# elasticNode.net
KiCad netlist of a schematic drawn in EAGLE
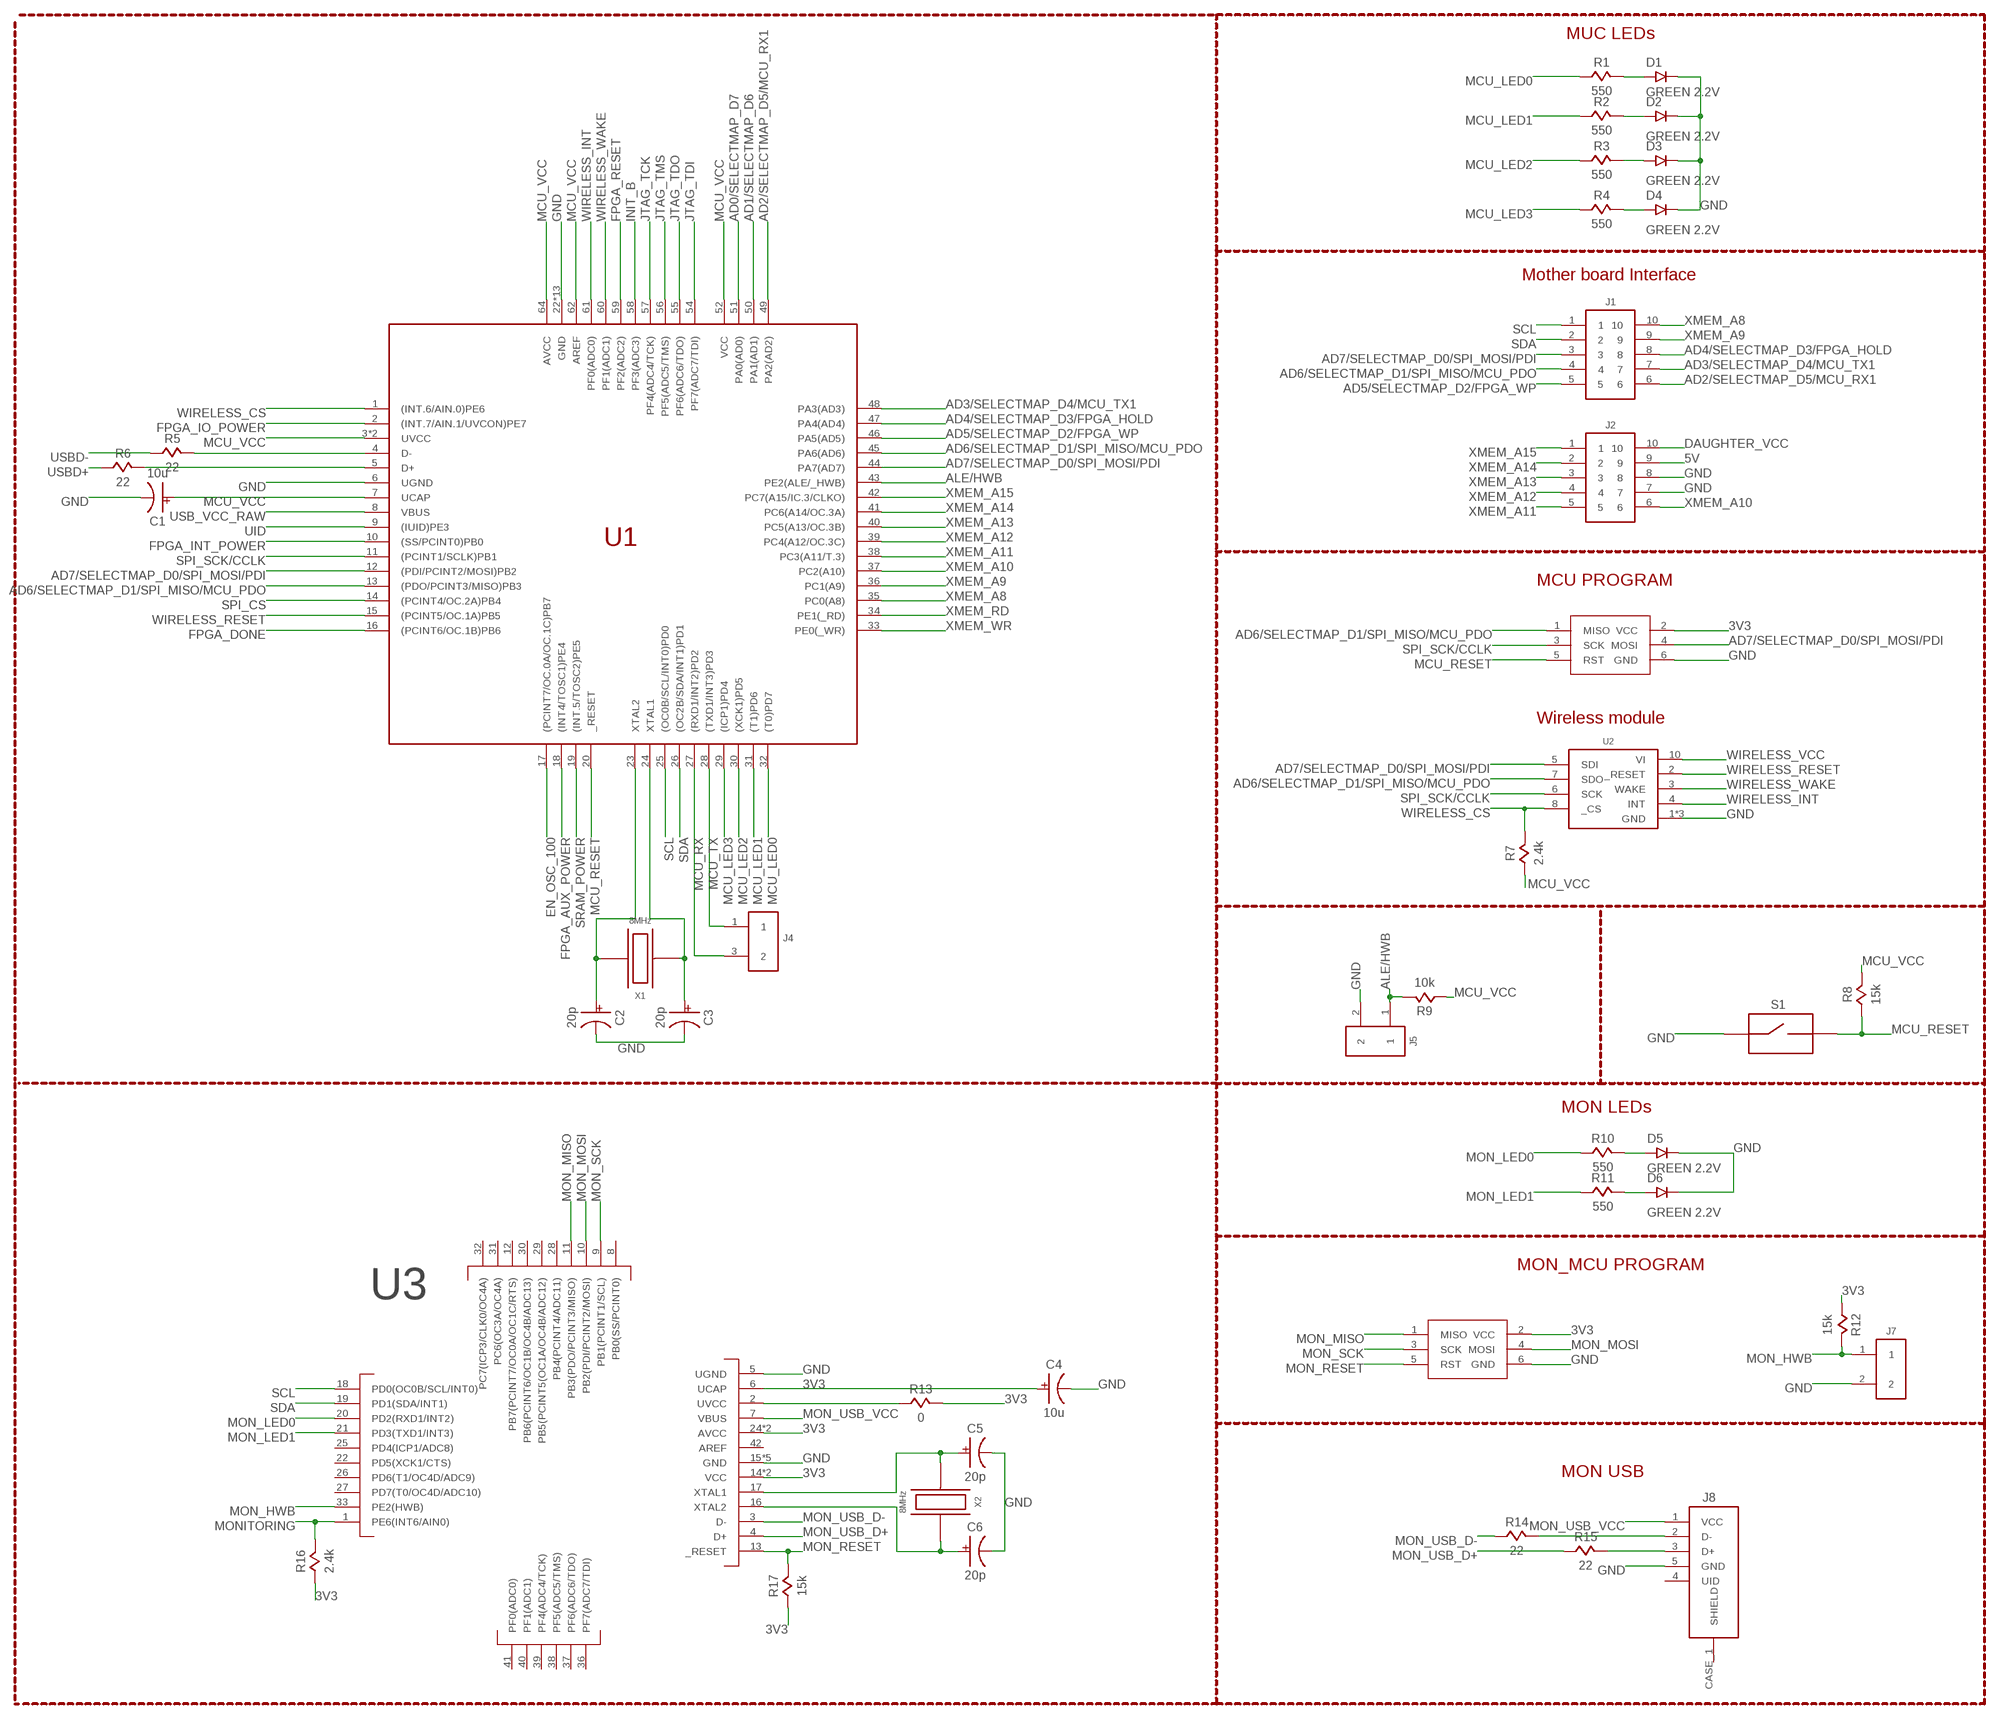
[diagram p0: schematic, sheet 1]
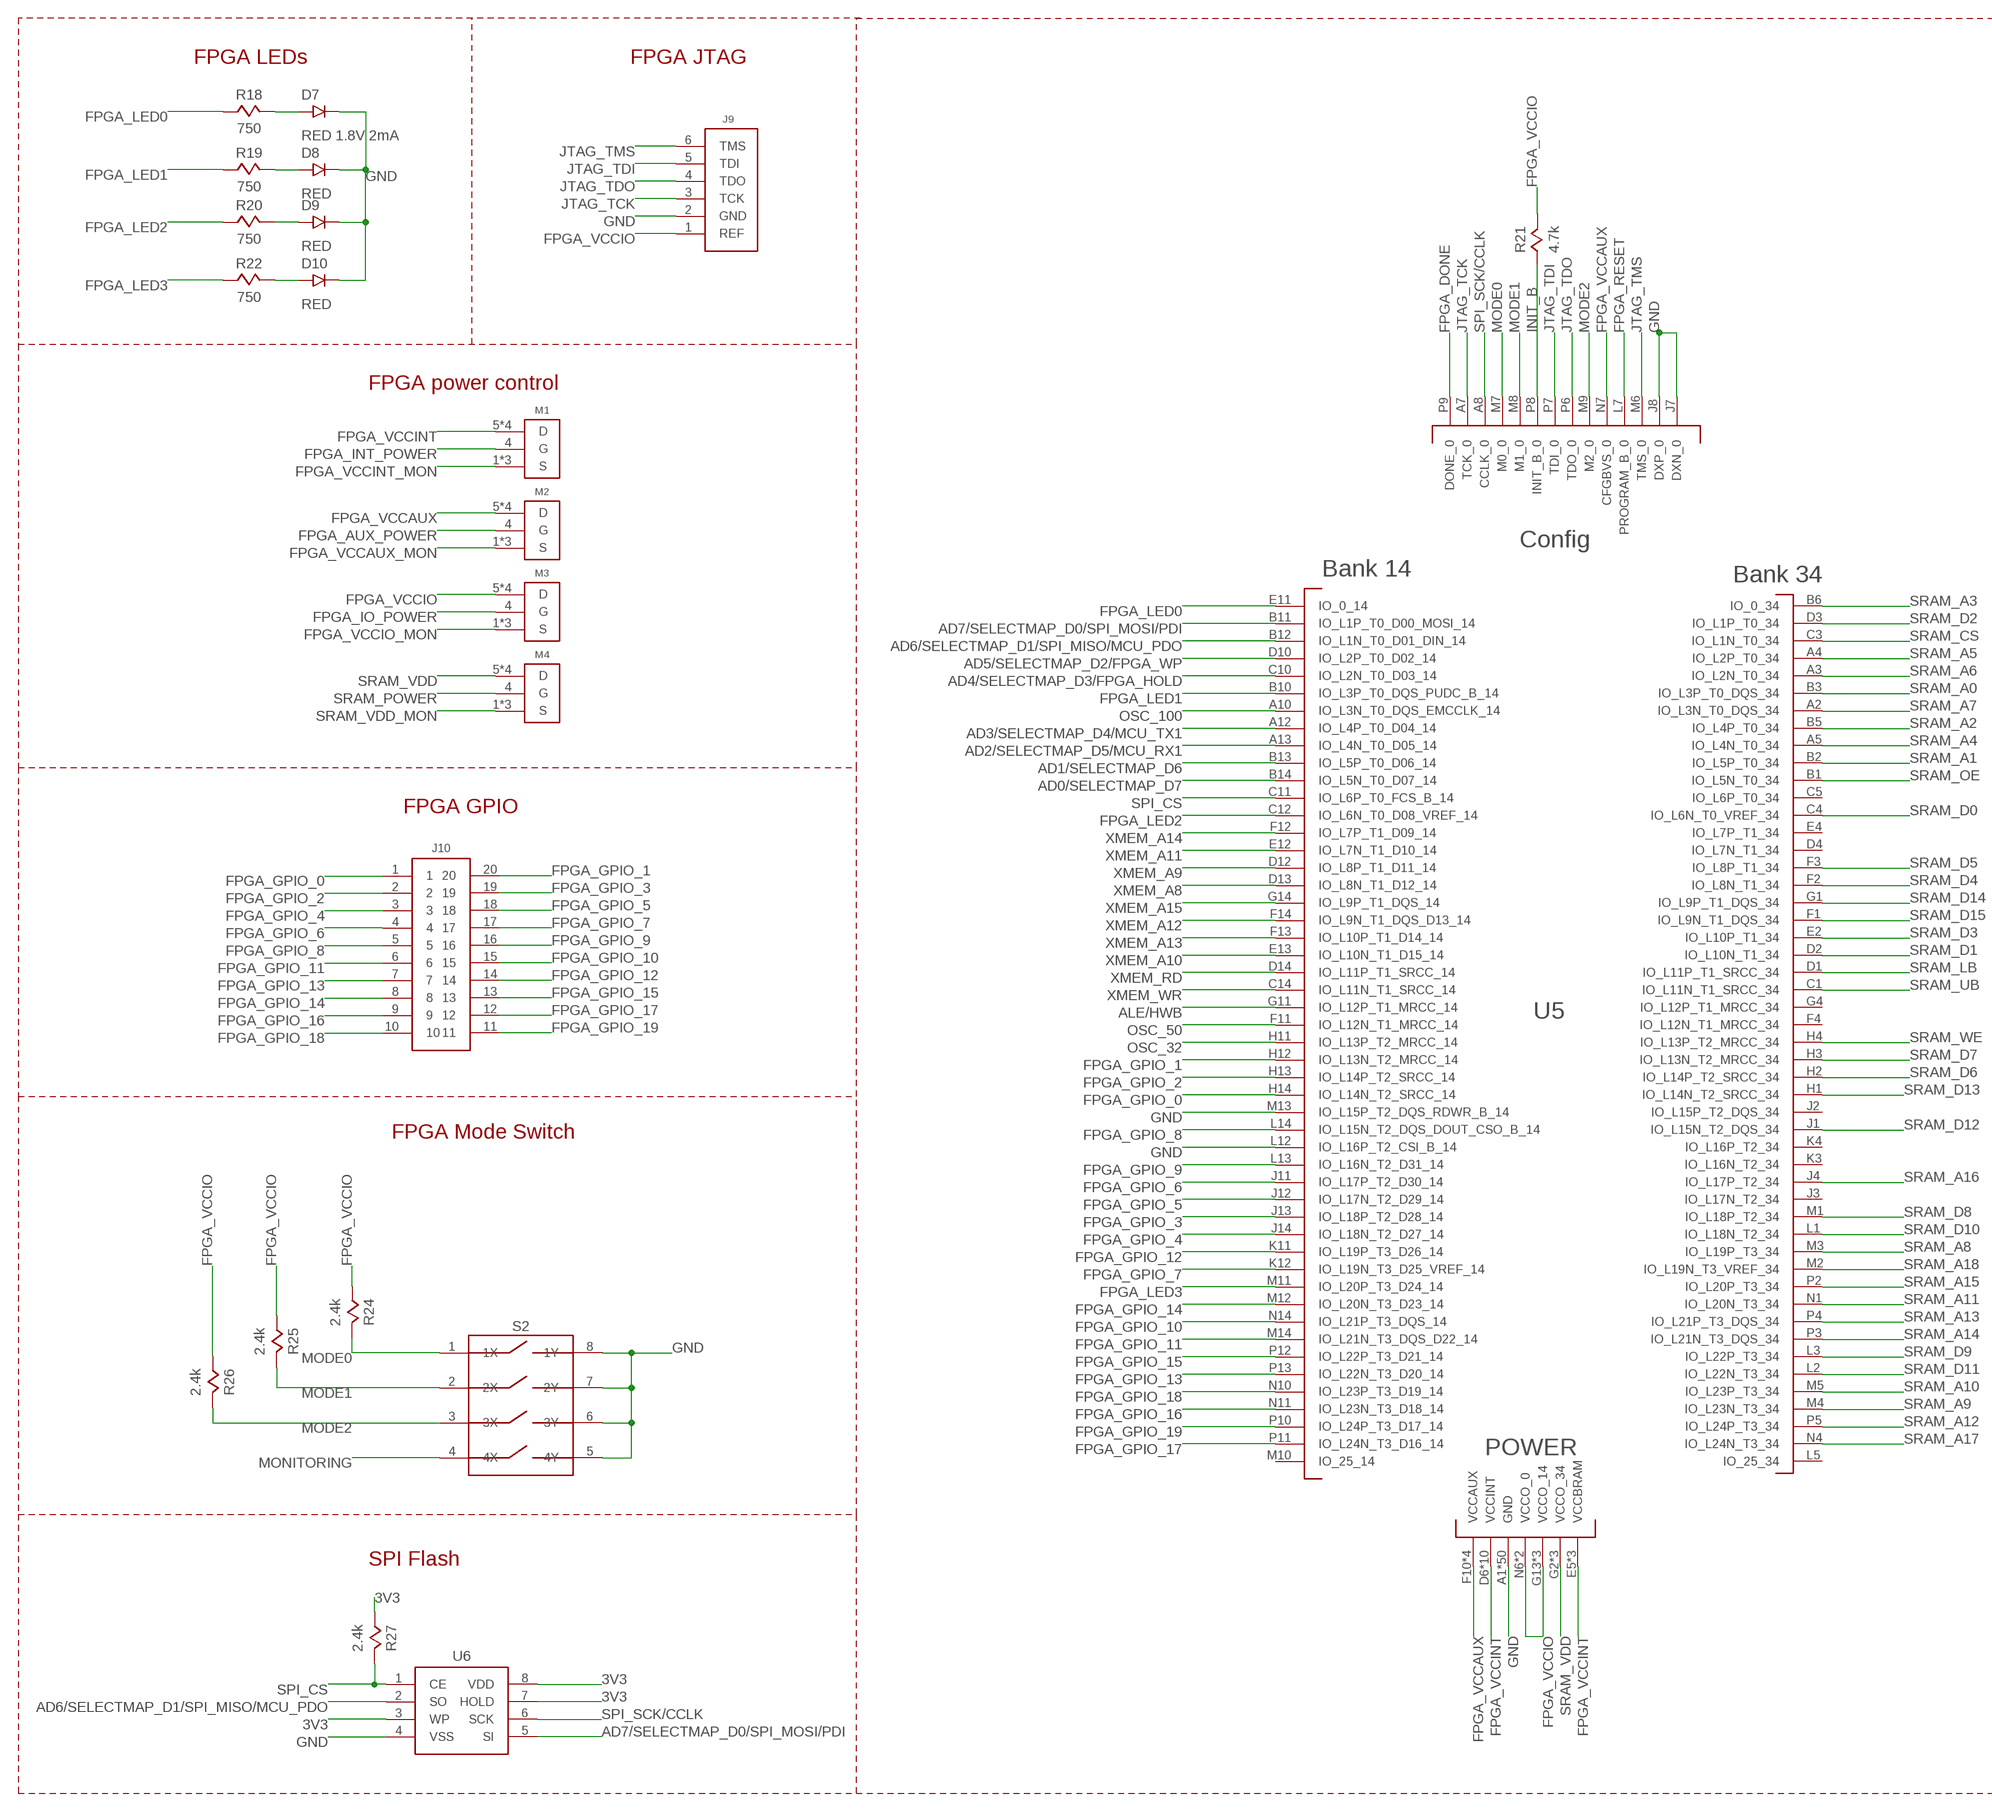
[diagram p1: schematic, sheet 2, part 1 of 2]
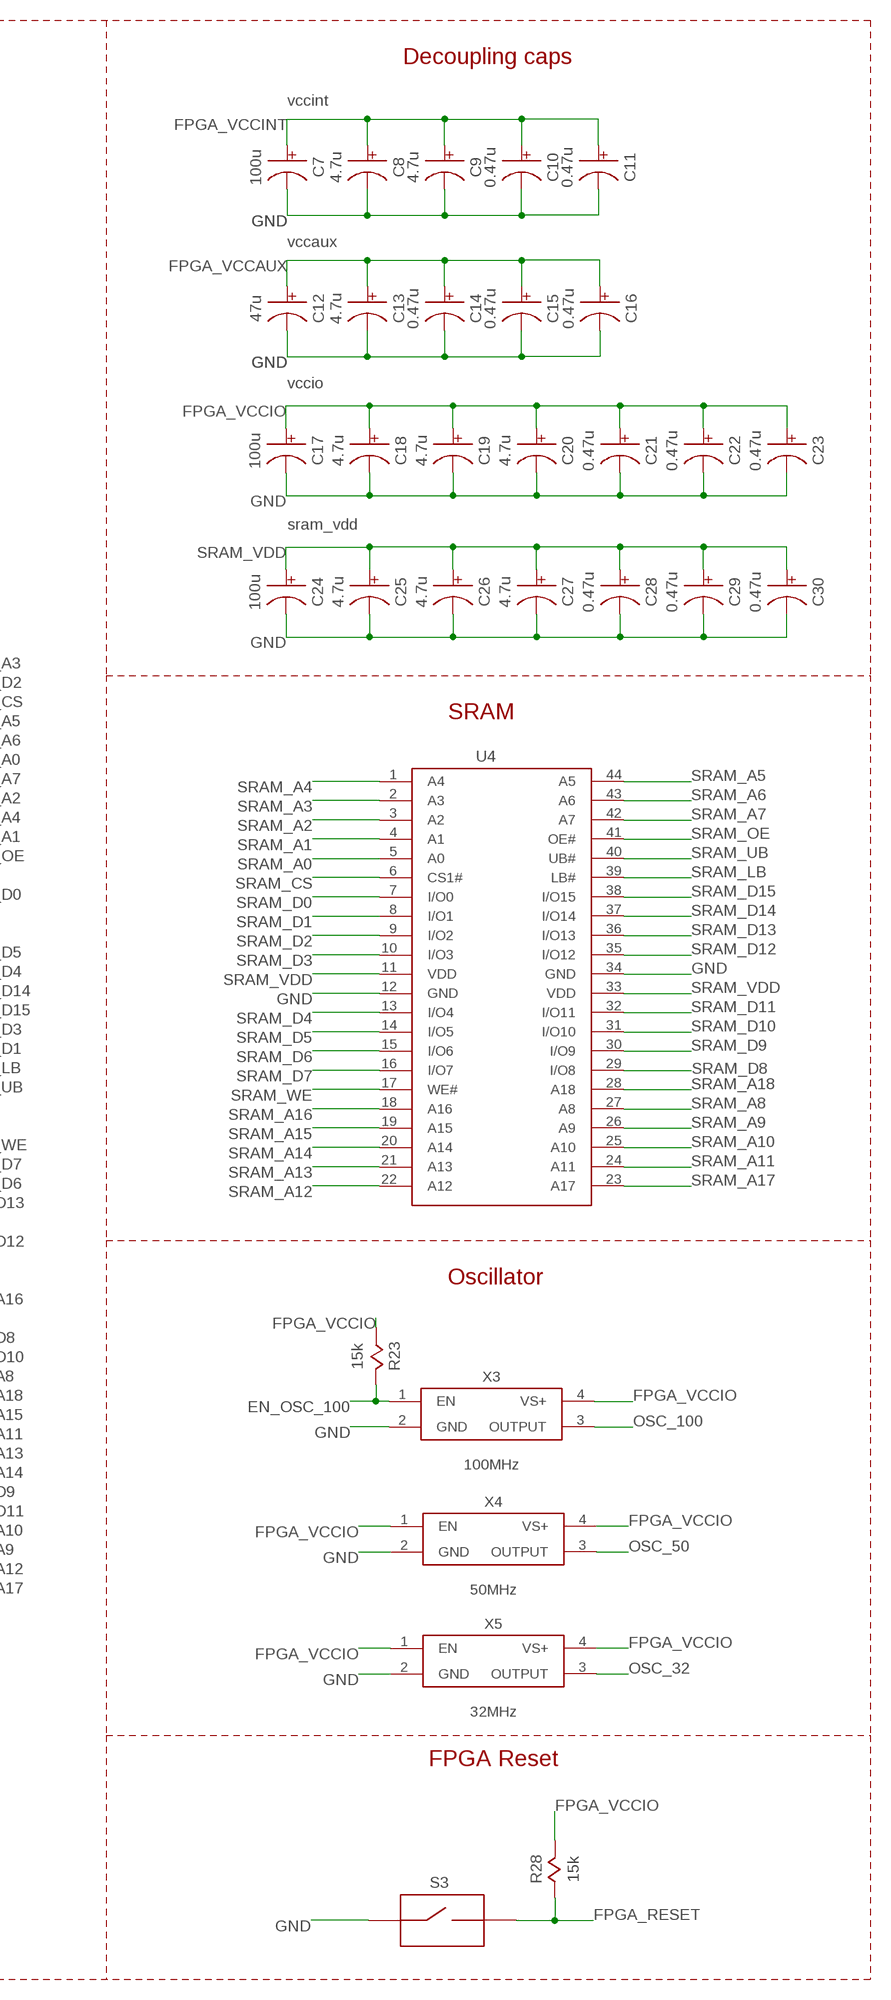
[diagram p2: schematic, sheet 2, part 2 of 2]
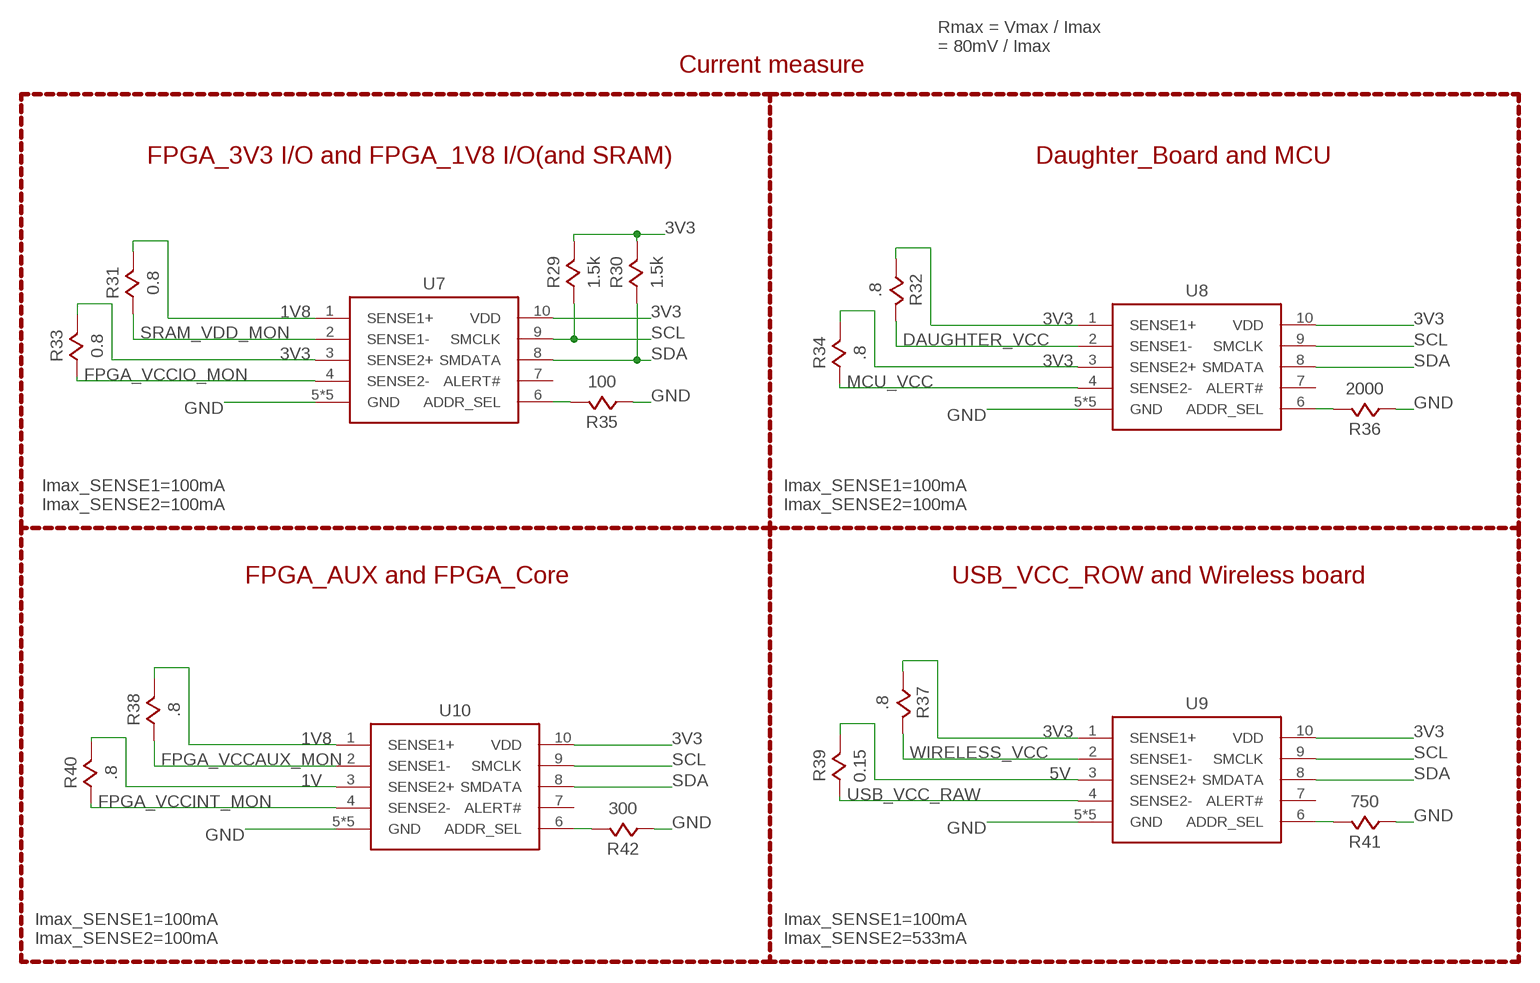
[diagram p3: schematic, sheet 3]
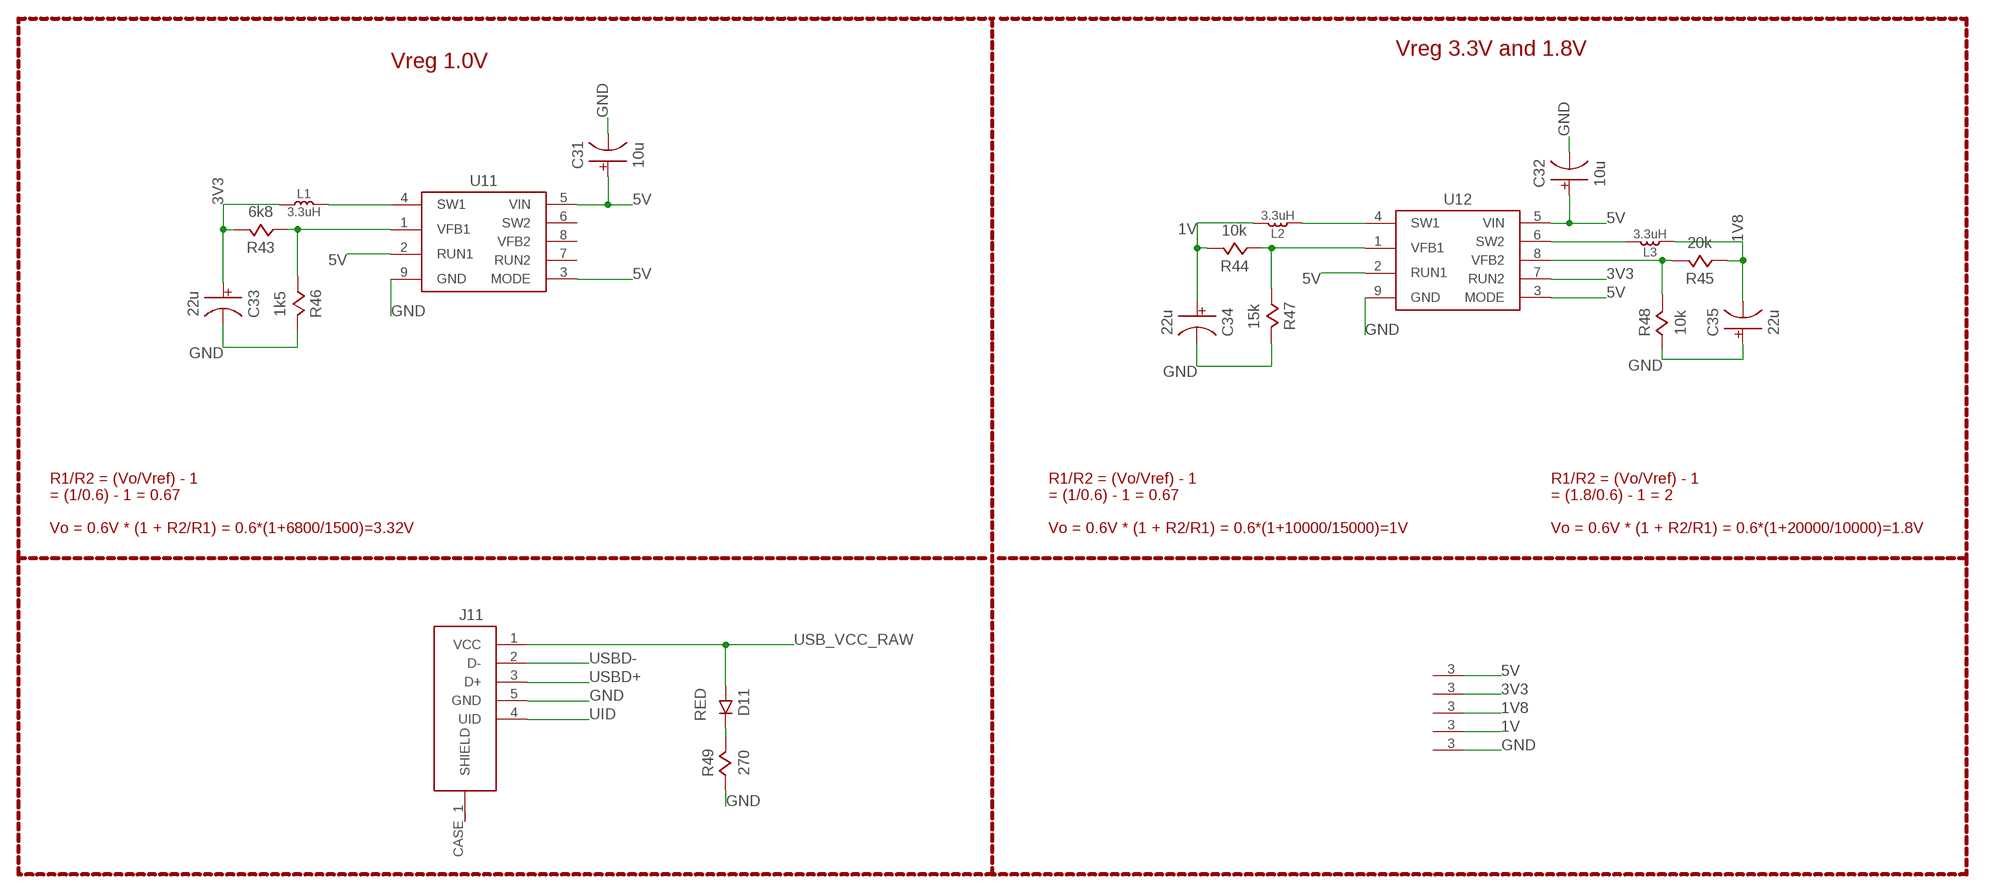
[diagram p4: schematic, sheet 4]

(export (version "E")
  (design (tool "Eeschema 10.0.6"))
  (components
    (comp (ref "C7")
      (value "100u")
      (footprint "eagle-import:1210")
      (libsource (lib "eagle-import") (part "CAPACITOR1210"))
    )
    (comp (ref "C8")
      (value "4.7u")
      (footprint "eagle-import:0805")
      (libsource (lib "eagle-import") (part "CAPACITOR0805"))
    )
    (comp (ref "C9")
      (value "4.7u")
      (footprint "eagle-import:0805")
      (libsource (lib "eagle-import") (part "CAPACITOR0805"))
    )
    (comp (ref "C10")
      (value "0.47u")
      (footprint "eagle-import:0805")
      (libsource (lib "eagle-import") (part "CAPACITOR0805"))
    )
    (comp (ref "C11")
      (value "0.47u")
      (footprint "eagle-import:0805")
      (libsource (lib "eagle-import") (part "CAPACITOR0805"))
    )
    (comp (ref "C12")
      (value "47u")
      (footprint "eagle-import:1210")
      (libsource (lib "eagle-import") (part "CAPACITOR1210"))
    )
    (comp (ref "C13")
      (value "4.7u")
      (footprint "eagle-import:0805")
      (libsource (lib "eagle-import") (part "CAPACITOR0805"))
    )
    (comp (ref "C14")
      (value "0.47u")
      (footprint "eagle-import:0805")
      (libsource (lib "eagle-import") (part "CAPACITOR0805"))
    )
    (comp (ref "C15")
      (value "0.47u")
      (footprint "eagle-import:0805")
      (libsource (lib "eagle-import") (part "CAPACITOR0805"))
    )
    (comp (ref "C16")
      (value "0.47u")
      (footprint "eagle-import:0805")
      (libsource (lib "eagle-import") (part "CAPACITOR0805"))
    )
    (comp (ref "C17")
      (value "100u")
      (footprint "eagle-import:1210")
      (libsource (lib "eagle-import") (part "CAPACITOR1210"))
    )
    (comp (ref "C18")
      (value "4.7u")
      (footprint "eagle-import:0805")
      (libsource (lib "eagle-import") (part "CAPACITOR0805"))
    )
    (comp (ref "C19")
      (value "4.7u")
      (footprint "eagle-import:0805")
      (libsource (lib "eagle-import") (part "CAPACITOR0805"))
    )
    (comp (ref "C20")
      (value "4.7u")
      (footprint "eagle-import:0805")
      (libsource (lib "eagle-import") (part "CAPACITOR0805"))
    )
    (comp (ref "C21")
      (value "0.47u")
      (footprint "eagle-import:0805")
      (libsource (lib "eagle-import") (part "CAPACITOR0805"))
    )
    (comp (ref "C22")
      (value "0.47u")
      (footprint "eagle-import:0805")
      (libsource (lib "eagle-import") (part "CAPACITOR0805"))
    )
    (comp (ref "C23")
      (value "0.47u")
      (footprint "eagle-import:0805")
      (libsource (lib "eagle-import") (part "CAPACITOR0805"))
    )
    (comp (ref "C24")
      (value "100u")
      (footprint "eagle-import:1210")
      (libsource (lib "eagle-import") (part "CAPACITOR1210"))
    )
    (comp (ref "C25")
      (value "4.7u")
      (footprint "eagle-import:0805")
      (libsource (lib "eagle-import") (part "CAPACITOR0805"))
    )
    (comp (ref "C26")
      (value "4.7u")
      (footprint "eagle-import:0805")
      (libsource (lib "eagle-import") (part "CAPACITOR0805"))
    )
    (comp (ref "C27")
      (value "4.7u")
      (footprint "eagle-import:0805")
      (libsource (lib "eagle-import") (part "CAPACITOR0805"))
    )
    (comp (ref "C28")
      (value "0.47u")
      (footprint "eagle-import:0805")
      (libsource (lib "eagle-import") (part "CAPACITOR0805"))
    )
    (comp (ref "C29")
      (value "0.47u")
      (footprint "eagle-import:0805")
      (libsource (lib "eagle-import") (part "CAPACITOR0805"))
    )
    (comp (ref "C30")
      (value "0.47u")
      (footprint "eagle-import:0805")
      (libsource (lib "eagle-import") (part "CAPACITOR0805"))
    )
    (comp (ref "D7")
      (value "RED 1.8V 2mA")
      (footprint "eagle-import:0805")
      (libsource (lib "eagle-import") (part "LED"))
    )
    (comp (ref "D8")
      (value "RED")
      (footprint "eagle-import:0805")
      (libsource (lib "eagle-import") (part "LED"))
    )
    (comp (ref "D9")
      (value "RED")
      (footprint "eagle-import:0805")
      (libsource (lib "eagle-import") (part "LED"))
    )
    (comp (ref "D10")
      (value "RED")
      (footprint "eagle-import:0805")
      (libsource (lib "eagle-import") (part "LED"))
    )
    (comp (ref "J9")
      (value "JTAG_CONN_6PINSMT")
      (footprint "eagle-import:6X1_JTAG")
      (libsource (lib "eagle-import") (part "JTAG_CONN_6PINSMT"))
    )
    (comp (ref "J10")
      (value "FEMALE_HEADER_10X2")
      (footprint "eagle-import:10X2_HEADER_SMT")
      (libsource (lib "eagle-import") (part "FEMALE_HEADER_10X2"))
    )
    (comp (ref "M1")
      (value "SISS23DN")
      (footprint "eagle-import:POWERPAK1212-8")
      (libsource (lib "eagle-import") (part "SISS23DN"))
    )
    (comp (ref "M2")
      (value "SISS23DN")
      (footprint "eagle-import:POWERPAK1212-8")
      (libsource (lib "eagle-import") (part "SISS23DN"))
    )
    (comp (ref "M3")
      (value "SISS23DN")
      (footprint "eagle-import:POWERPAK1212-8")
      (libsource (lib "eagle-import") (part "SISS23DN"))
    )
    (comp (ref "M4")
      (value "SISS23DN")
      (footprint "eagle-import:POWERPAK1212-8")
      (libsource (lib "eagle-import") (part "SISS23DN"))
    )
    (comp (ref "R18")
      (value "750")
      (footprint "eagle-import:0805")
      (libsource (lib "eagle-import") (part "RESISTOR"))
    )
    (comp (ref "R19")
      (value "750")
      (footprint "eagle-import:0805")
      (libsource (lib "eagle-import") (part "RESISTOR"))
    )
    (comp (ref "R20")
      (value "750")
      (footprint "eagle-import:0805")
      (libsource (lib "eagle-import") (part "RESISTOR"))
    )
    (comp (ref "R21")
      (value "4.7k")
      (footprint "eagle-import:0805")
      (libsource (lib "eagle-import") (part "RESISTOR"))
    )
    (comp (ref "R22")
      (value "750")
      (footprint "eagle-import:0805")
      (libsource (lib "eagle-import") (part "RESISTOR"))
    )
    (comp (ref "R23")
      (value "15k")
      (footprint "eagle-import:0805")
      (libsource (lib "eagle-import") (part "RESISTOR"))
    )
    (comp (ref "R24")
      (value "2.4k")
      (footprint "eagle-import:0805")
      (libsource (lib "eagle-import") (part "RESISTOR"))
    )
    (comp (ref "R25")
      (value "2.4k")
      (footprint "eagle-import:0805")
      (libsource (lib "eagle-import") (part "RESISTOR"))
    )
    (comp (ref "R26")
      (value "2.4k")
      (footprint "eagle-import:0805")
      (libsource (lib "eagle-import") (part "RESISTOR"))
    )
    (comp (ref "R27")
      (value "2.4k")
      (footprint "eagle-import:0805")
      (libsource (lib "eagle-import") (part "RESISTOR"))
    )
    (comp (ref "R28")
      (value "15k")
      (footprint "eagle-import:0805")
      (libsource (lib "eagle-import") (part "RESISTOR"))
    )
    (comp (ref "S2")
      (value "SPST_DIP_4")
      (footprint "eagle-import:SPST_DIP4_SMT")
      (libsource (lib "eagle-import") (part "SPST_DIP_4"))
    )
    (comp (ref "S3")
      (value "SPST_BUTTON2PIN_SMT")
      (footprint "eagle-import:SPST_2PIN_SMT")
      (libsource (lib "eagle-import") (part "SPST_BUTTON2PIN_SMT"))
    )
    (comp (ref "U4")
      (value "IS66WV51216EALL")
      (footprint "eagle-import:TSOP44")
      (libsource (lib "eagle-import") (part "IS66WV51216EALL"))
    )
    (comp (ref "U5")
      (value "SPARTAN7-LX15")
      (footprint "eagle-import:FTGB196")
      (libsource (lib "eagle-import") (part "SPARTAN7-LX15"))
    )
    (comp (ref "U6")
      (value "SST26VF032BWDFN")
      (footprint "eagle-import:WDFN8")
      (libsource (lib "eagle-import") (part "SST26VF032BWDFN"))
    )
    (comp (ref "X3")
      (value "100MHz")
      (footprint "eagle-import:3.2X2.5_OSC")
      (libsource (lib "eagle-import") (part "OSCILLATOR3.2X2.5"))
    )
    (comp (ref "X4")
      (value "50MHz")
      (footprint "eagle-import:3.2X2.5_OSC")
      (libsource (lib "eagle-import") (part "OSCILLATOR3.2X2.5"))
    )
    (comp (ref "X5")
      (value "32MHz")
      (footprint "eagle-import:3.2X2.5_OSC")
      (libsource (lib "eagle-import") (part "OSCILLATOR3.2X2.5"))
    )
    (comp (ref "C1")
      (value "10u")
      (footprint "eagle-import:0805")
      (libsource (lib "eagle-import") (part "CAPACITOR0805"))
    )
    (comp (ref "C2")
      (value "20p")
      (footprint "eagle-import:0805")
      (libsource (lib "eagle-import") (part "CAPACITOR0805"))
    )
    (comp (ref "C3")
      (value "20p")
      (footprint "eagle-import:0805")
      (libsource (lib "eagle-import") (part "CAPACITOR0805"))
    )
    (comp (ref "C4")
      (value "10u")
      (footprint "eagle-import:0805")
      (libsource (lib "eagle-import") (part "CAPACITOR0805"))
    )
    (comp (ref "C5")
      (value "20p")
      (footprint "eagle-import:0805")
      (libsource (lib "eagle-import") (part "CAPACITOR0805"))
    )
    (comp (ref "C6")
      (value "20p")
      (footprint "eagle-import:0805")
      (libsource (lib "eagle-import") (part "CAPACITOR0805"))
    )
    (comp (ref "D1")
      (value "GREEN 2.2V")
      (footprint "eagle-import:0805")
      (libsource (lib "eagle-import") (part "LED"))
    )
    (comp (ref "D2")
      (value "GREEN 2.2V")
      (footprint "eagle-import:0805")
      (libsource (lib "eagle-import") (part "LED"))
    )
    (comp (ref "D3")
      (value "GREEN 2.2V")
      (footprint "eagle-import:0805")
      (libsource (lib "eagle-import") (part "LED"))
    )
    (comp (ref "D4")
      (value "GREEN 2.2V")
      (footprint "eagle-import:0805")
      (libsource (lib "eagle-import") (part "LED"))
    )
    (comp (ref "D5")
      (value "GREEN 2.2V")
      (footprint "eagle-import:0805")
      (libsource (lib "eagle-import") (part "LED"))
    )
    (comp (ref "D6")
      (value "GREEN 2.2V")
      (footprint "eagle-import:0805")
      (libsource (lib "eagle-import") (part "LED"))
    )
    (comp (ref "J1")
      (value "FEMALE_HEADER_5X2")
      (footprint "eagle-import:5X2_HEADER_SMT_1.27")
      (libsource (lib "eagle-import") (part "FEMALE_HEADER_5X2"))
    )
    (comp (ref "J2")
      (value "FEMALE_HEADER_5X2")
      (footprint "eagle-import:5X2_HEADER_SMT_1.27")
      (libsource (lib "eagle-import") (part "FEMALE_HEADER_5X2"))
    )
    (comp (ref "J3")
      (value "ISP_CONN_6PIN")
      (footprint "eagle-import:ICSP_SMT")
      (fields (field (name "SPICEPREFIX") "X"))
      (libsource (lib "eagle-import") (part "ISP_CONN_6PIN"))
    )
    (comp (ref "J4")
      (value "FEMALE_HEADER_2X1")
      (footprint "eagle-import:2X1_HEADER")
      (libsource (lib "eagle-import") (part "FEMALE_HEADER_2X1"))
    )
    (comp (ref "J5")
      (value "JUMPER")
      (footprint "eagle-import:JUMPER_SMT")
      (libsource (lib "eagle-import") (part "JUMPER"))
    )
    (comp (ref "J6")
      (value "ISP_CONN_6PIN")
      (footprint "eagle-import:ICSP_SMT")
      (libsource (lib "eagle-import") (part "ISP_CONN_6PIN"))
    )
    (comp (ref "J7")
      (value "JUMPER")
      (footprint "eagle-import:JUMPER_SMT")
      (libsource (lib "eagle-import") (part "JUMPER"))
    )
    (comp (ref "J8")
      (value "USB_CONNMICRO_SMT")
      (footprint "eagle-import:USB_MICRO_B_SMT")
      (libsource (lib "eagle-import") (part "USB_CONNMICRO_SMT"))
    )
    (comp (ref "R1")
      (value "550")
      (footprint "eagle-import:0805")
      (libsource (lib "eagle-import") (part "RESISTOR"))
    )
    (comp (ref "R2")
      (value "550")
      (footprint "eagle-import:0805")
      (libsource (lib "eagle-import") (part "RESISTOR"))
    )
    (comp (ref "R3")
      (value "550")
      (footprint "eagle-import:0805")
      (libsource (lib "eagle-import") (part "RESISTOR"))
    )
    (comp (ref "R4")
      (value "550")
      (footprint "eagle-import:0805")
      (libsource (lib "eagle-import") (part "RESISTOR"))
    )
    (comp (ref "R5")
      (value "22")
      (footprint "eagle-import:0805")
      (libsource (lib "eagle-import") (part "RESISTOR"))
    )
    (comp (ref "R6")
      (value "22")
      (footprint "eagle-import:0805")
      (libsource (lib "eagle-import") (part "RESISTOR"))
    )
    (comp (ref "R7")
      (value "2.4k")
      (footprint "eagle-import:0805")
      (libsource (lib "eagle-import") (part "RESISTOR"))
    )
    (comp (ref "R8")
      (value "15k")
      (footprint "eagle-import:0805")
      (libsource (lib "eagle-import") (part "RESISTOR"))
    )
    (comp (ref "R9")
      (value "10k")
      (footprint "eagle-import:0805")
      (libsource (lib "eagle-import") (part "RESISTOR"))
    )
    (comp (ref "R10")
      (value "550")
      (footprint "eagle-import:0805")
      (libsource (lib "eagle-import") (part "RESISTOR"))
    )
    (comp (ref "R11")
      (value "550")
      (footprint "eagle-import:0805")
      (libsource (lib "eagle-import") (part "RESISTOR"))
    )
    (comp (ref "R12")
      (value "15k")
      (footprint "eagle-import:0805")
      (libsource (lib "eagle-import") (part "RESISTOR"))
    )
    (comp (ref "R13")
      (value "0")
      (footprint "eagle-import:0805")
      (libsource (lib "eagle-import") (part "RESISTOR"))
    )
    (comp (ref "R14")
      (value "22")
      (footprint "eagle-import:0805")
      (libsource (lib "eagle-import") (part "RESISTOR"))
    )
    (comp (ref "R15")
      (value "22")
      (footprint "eagle-import:0805")
      (libsource (lib "eagle-import") (part "RESISTOR"))
    )
    (comp (ref "R16")
      (value "2.4k")
      (footprint "eagle-import:0805")
      (libsource (lib "eagle-import") (part "RESISTOR"))
    )
    (comp (ref "R17")
      (value "15k")
      (footprint "eagle-import:0805")
      (libsource (lib "eagle-import") (part "RESISTOR"))
    )
    (comp (ref "S1")
      (value "SPST_BUTTON2PIN_SMT")
      (footprint "eagle-import:SPST_2PIN_SMT")
      (libsource (lib "eagle-import") (part "SPST_BUTTON2PIN_SMT"))
    )
    (comp (ref "U1")
      (value "AT90USB128")
      (footprint "eagle-import:QFN64")
      (libsource (lib "eagle-import") (part "AT90USB128"))
    )
    (comp (ref "U2")
      (value "MRF24J40MA")
      (footprint "eagle-import:MRF24J40MA")
      (libsource (lib "eagle-import") (part "MRF24J40MA"))
    )
    (comp (ref "U3")
      (value "ATMEGA32U4QFN")
      (footprint "eagle-import:QFN44")
      (libsource (lib "eagle-import") (part "ATMEGA32U4QFN"))
    )
    (comp (ref "X1")
      (value "8MHz")
      (footprint "eagle-import:3.2X2.5_OSC")
      (libsource (lib "eagle-import") (part "QUARTZ"))
    )
    (comp (ref "X2")
      (value "8MHz")
      (footprint "eagle-import:3.2X2.5_OSC")
      (libsource (lib "eagle-import") (part "QUARTZ"))
    )
    (comp (ref "R29")
      (value "1.5k")
      (footprint "eagle-import:0805")
      (libsource (lib "eagle-import") (part "RESISTOR"))
    )
    (comp (ref "R30")
      (value "1.5k")
      (footprint "eagle-import:0805")
      (libsource (lib "eagle-import") (part "RESISTOR"))
    )
    (comp (ref "R31")
      (value "0.8")
      (footprint "eagle-import:0805")
      (libsource (lib "eagle-import") (part "RESISTOR"))
    )
    (comp (ref "R32")
      (value ".8")
      (footprint "eagle-import:0805")
      (libsource (lib "eagle-import") (part "RESISTOR"))
    )
    (comp (ref "R33")
      (value "0.8")
      (footprint "eagle-import:0805")
      (libsource (lib "eagle-import") (part "RESISTOR"))
    )
    (comp (ref "R34")
      (value ".8")
      (footprint "eagle-import:0805")
      (libsource (lib "eagle-import") (part "RESISTOR"))
    )
    (comp (ref "R35")
      (value "100")
      (footprint "eagle-import:0805")
      (libsource (lib "eagle-import") (part "RESISTOR"))
    )
    (comp (ref "R36")
      (value "2000")
      (footprint "eagle-import:0805")
      (libsource (lib "eagle-import") (part "RESISTOR"))
    )
    (comp (ref "R37")
      (value ".8")
      (footprint "eagle-import:0805")
      (libsource (lib "eagle-import") (part "RESISTOR"))
    )
    (comp (ref "R38")
      (value ".8")
      (footprint "eagle-import:0805")
      (libsource (lib "eagle-import") (part "RESISTOR"))
    )
    (comp (ref "R39")
      (value "0.15")
      (footprint "eagle-import:0805")
      (libsource (lib "eagle-import") (part "RESISTOR"))
    )
    (comp (ref "R40")
      (value ".8")
      (footprint "eagle-import:0805")
      (libsource (lib "eagle-import") (part "RESISTOR"))
    )
    (comp (ref "R41")
      (value "750")
      (footprint "eagle-import:0805")
      (libsource (lib "eagle-import") (part "RESISTOR"))
    )
    (comp (ref "R42")
      (value "300")
      (footprint "eagle-import:0805")
      (libsource (lib "eagle-import") (part "RESISTOR"))
    )
    (comp (ref "U7")
      (value "PAC1720")
      (footprint "eagle-import:VDFN10")
      (libsource (lib "eagle-import") (part "PAC1720"))
    )
    (comp (ref "U8")
      (value "PAC1720")
      (footprint "eagle-import:VDFN10")
      (libsource (lib "eagle-import") (part "PAC1720"))
    )
    (comp (ref "U9")
      (value "PAC1720")
      (footprint "eagle-import:VDFN10")
      (libsource (lib "eagle-import") (part "PAC1720"))
    )
    (comp (ref "U10")
      (value "PAC1720")
      (footprint "eagle-import:VDFN10")
      (libsource (lib "eagle-import") (part "PAC1720"))
    )
    (comp (ref "C31")
      (value "10u")
      (footprint "eagle-import:0805")
      (libsource (lib "eagle-import") (part "CAPACITOR0805"))
    )
    (comp (ref "C32")
      (value "10u")
      (footprint "eagle-import:0805")
      (libsource (lib "eagle-import") (part "CAPACITOR0805"))
    )
    (comp (ref "C33")
      (value "22u")
      (footprint "eagle-import:0805")
      (libsource (lib "eagle-import") (part "CAPACITOR0805"))
    )
    (comp (ref "C34")
      (value "22u")
      (footprint "eagle-import:0805")
      (libsource (lib "eagle-import") (part "CAPACITOR0805"))
    )
    (comp (ref "C35")
      (value "22u")
      (footprint "eagle-import:0805")
      (libsource (lib "eagle-import") (part "CAPACITOR0805"))
    )
    (comp (ref "D11")
      (value "RED")
      (footprint "eagle-import:0805")
      (libsource (lib "eagle-import") (part "LED"))
    )
    (comp (ref "J11")
      (value "USB_CONNMICRO_SMT")
      (footprint "eagle-import:USB_MICRO_B_SMT")
      (libsource (lib "eagle-import") (part "USB_CONNMICRO_SMT"))
    )
    (comp (ref "L1")
      (value "3.3uH")
      (footprint "eagle-import:0805")
      (libsource (lib "eagle-import") (part "INDUCTOR"))
    )
    (comp (ref "L2")
      (value "3.3uH")
      (footprint "eagle-import:0805")
      (libsource (lib "eagle-import") (part "INDUCTOR"))
    )
    (comp (ref "L3")
      (value "3.3uH")
      (footprint "eagle-import:0805")
      (libsource (lib "eagle-import") (part "INDUCTOR"))
    )
    (comp (ref "R43")
      (value "6k8")
      (footprint "eagle-import:0805")
      (libsource (lib "eagle-import") (part "RESISTOR"))
    )
    (comp (ref "R44")
      (value "10k")
      (footprint "eagle-import:0805")
      (libsource (lib "eagle-import") (part "RESISTOR"))
    )
    (comp (ref "R45")
      (value "20k")
      (footprint "eagle-import:0805")
      (libsource (lib "eagle-import") (part "RESISTOR"))
    )
    (comp (ref "R46")
      (value "1k5")
      (footprint "eagle-import:0805")
      (libsource (lib "eagle-import") (part "RESISTOR"))
    )
    (comp (ref "R47")
      (value "15k")
      (footprint "eagle-import:0805")
      (libsource (lib "eagle-import") (part "RESISTOR"))
    )
    (comp (ref "R48")
      (value "10k")
      (footprint "eagle-import:0805")
      (libsource (lib "eagle-import") (part "RESISTOR"))
    )
    (comp (ref "R49")
      (value "270")
      (footprint "eagle-import:0805")
      (libsource (lib "eagle-import") (part "RESISTOR"))
    )
    (comp (ref "TP1")
      (value "TEST_POINTTHT")
      (footprint "eagle-import:THT")
      (libsource (lib "eagle-import") (part "TEST_POINTTHT"))
    )
    (comp (ref "TP2")
      (value "TEST_POINTTHT")
      (footprint "eagle-import:THT")
      (libsource (lib "eagle-import") (part "TEST_POINTTHT"))
    )
    (comp (ref "TP3")
      (value "TEST_POINTTHT")
      (footprint "eagle-import:THT")
      (libsource (lib "eagle-import") (part "TEST_POINTTHT"))
    )
    (comp (ref "TP4")
      (value "TEST_POINTTHT")
      (footprint "eagle-import:THT")
      (libsource (lib "eagle-import") (part "TEST_POINTTHT"))
    )
    (comp (ref "TP5")
      (value "TEST_POINTTHT")
      (footprint "eagle-import:THT")
      (libsource (lib "eagle-import") (part "TEST_POINTTHT"))
    )
    (comp (ref "U11")
      (value "LTC3419DFN")
      (footprint "eagle-import:DFN8")
      (libsource (lib "eagle-import") (part "LTC3419DFN"))
    )
    (comp (ref "U12")
      (value "LTC3419DFN")
      (footprint "eagle-import:DFN8")
      (libsource (lib "eagle-import") (part "LTC3419DFN"))
    )
  )
  (nets
    (net (code "1") (name "1V") (class "Default")
      (node (ref "C34") (pin "1") (pinfunction "P$1_1") (pintype "bidirectional"))
      (node (ref "L2") (pin "2") (pinfunction "P$2_2") (pintype "bidirectional"))
      (node (ref "R40") (pin "2") (pinfunction "2_2") (pintype "bidirectional"))
      (node (ref "R44") (pin "2") (pinfunction "2_2") (pintype "bidirectional"))
      (node (ref "TP4") (pin "3") (pinfunction ">NAME_3") (pintype "bidirectional"))
      (node (ref "U10") (pin "3") (pinfunction "SENSE2+_3") (pintype "bidirectional"))
    )
    (net (code "2") (name "1V8") (class "Default")
      (node (ref "C35") (pin "2") (pinfunction "P$2_2") (pintype "bidirectional"))
      (node (ref "L3") (pin "1") (pinfunction "P$1_1") (pintype "bidirectional"))
      (node (ref "R31") (pin "2") (pinfunction "2_2") (pintype "bidirectional"))
      (node (ref "R38") (pin "2") (pinfunction "2_2") (pintype "bidirectional"))
      (node (ref "R45") (pin "1") (pinfunction "1_1") (pintype "bidirectional"))
      (node (ref "TP3") (pin "3") (pinfunction ">NAME_3") (pintype "bidirectional"))
      (node (ref "U10") (pin "1") (pinfunction "SENSE1+_1") (pintype "bidirectional"))
      (node (ref "U7") (pin "1") (pinfunction "SENSE1+_1") (pintype "bidirectional"))
    )
    (net (code "3") (name "3V3") (class "Default")
      (node (ref "C33") (pin "1") (pinfunction "P$1_1") (pintype "bidirectional"))
      (node (ref "C4") (pin "1") (pinfunction "P$1_1") (pintype "bidirectional"))
      (node (ref "J3") (pin "2") (pinfunction "VCC_2") (pintype "bidirectional"))
      (node (ref "J6") (pin "2") (pinfunction "VCC_2") (pintype "bidirectional"))
      (node (ref "L1") (pin "1") (pinfunction "P$1_1") (pintype "bidirectional"))
      (node (ref "R12") (pin "1") (pinfunction "1_1") (pintype "bidirectional"))
      (node (ref "R13") (pin "2") (pinfunction "2_2") (pintype "bidirectional"))
      (node (ref "R16") (pin "1") (pinfunction "1_1") (pintype "bidirectional"))
      (node (ref "R17") (pin "1") (pinfunction "1_1") (pintype "bidirectional"))
      (node (ref "R27") (pin "1") (pinfunction "1_1") (pintype "bidirectional"))
      (node (ref "R29") (pin "2") (pinfunction "2_2") (pintype "bidirectional"))
      (node (ref "R30") (pin "2") (pinfunction "2_2") (pintype "bidirectional"))
      (node (ref "R32") (pin "2") (pinfunction "2_2") (pintype "bidirectional"))
      (node (ref "R33") (pin "2") (pinfunction "2_2") (pintype "bidirectional"))
      (node (ref "R34") (pin "2") (pinfunction "2_2") (pintype "bidirectional"))
      (node (ref "R37") (pin "2") (pinfunction "2_2") (pintype "bidirectional"))
      (node (ref "R43") (pin "2") (pinfunction "2_2") (pintype "bidirectional"))
      (node (ref "TP2") (pin "3") (pinfunction ">NAME_3") (pintype "bidirectional"))
      (node (ref "U10") (pin "10") (pinfunction "VDD_10") (pintype "bidirectional"))
      (node (ref "U12") (pin "7") (pinfunction "RUN2_7") (pintype "bidirectional"))
      (node (ref "U3") (pin "14") (pinfunction "VCC_14") (pintype "bidirectional"))
      (node (ref "U3") (pin "24") (pinfunction "AVCC_24") (pintype "bidirectional"))
      (node (ref "U3") (pin "34") (pinfunction "VCC_34") (pintype "bidirectional"))
      (node (ref "U3") (pin "44") (pinfunction "AVCC_44") (pintype "bidirectional"))
      (node (ref "U3") (pin "6") (pinfunction "UCAP_6") (pintype "bidirectional"))
      (node (ref "U6") (pin "3") (pinfunction "WP_3") (pintype "bidirectional"))
      (node (ref "U6") (pin "7") (pinfunction "HOLD_7") (pintype "bidirectional"))
      (node (ref "U6") (pin "8") (pinfunction "VDD_8") (pintype "bidirectional"))
      (node (ref "U7") (pin "10") (pinfunction "VDD_10") (pintype "bidirectional"))
      (node (ref "U7") (pin "3") (pinfunction "SENSE2+_3") (pintype "bidirectional"))
      (node (ref "U8") (pin "1") (pinfunction "SENSE1+_1") (pintype "bidirectional"))
      (node (ref "U8") (pin "10") (pinfunction "VDD_10") (pintype "bidirectional"))
      (node (ref "U8") (pin "3") (pinfunction "SENSE2+_3") (pintype "bidirectional"))
      (node (ref "U9") (pin "1") (pinfunction "SENSE1+_1") (pintype "bidirectional"))
      (node (ref "U9") (pin "10") (pinfunction "VDD_10") (pintype "bidirectional"))
    )
    (net (code "4") (name "5V") (class "Default")
      (node (ref "C31") (pin "1") (pinfunction "P$1_1") (pintype "bidirectional"))
      (node (ref "C32") (pin "1") (pinfunction "P$1_1") (pintype "bidirectional"))
      (node (ref "J2") (pin "9") (pinfunction "9_9") (pintype "bidirectional"))
      (node (ref "R39") (pin "2") (pinfunction "2_2") (pintype "bidirectional"))
      (node (ref "TP1") (pin "3") (pinfunction ">NAME_3") (pintype "bidirectional"))
      (node (ref "U11") (pin "2") (pinfunction "RUN1_2") (pintype "bidirectional"))
      (node (ref "U11") (pin "3") (pinfunction "MODE_3") (pintype "bidirectional"))
      (node (ref "U11") (pin "5") (pinfunction "VIN_5") (pintype "bidirectional"))
      (node (ref "U12") (pin "2") (pinfunction "RUN1_2") (pintype "bidirectional"))
      (node (ref "U12") (pin "3") (pinfunction "MODE_3") (pintype "bidirectional"))
      (node (ref "U12") (pin "5") (pinfunction "VIN_5") (pintype "bidirectional"))
      (node (ref "U9") (pin "3") (pinfunction "SENSE2+_3") (pintype "bidirectional"))
    )
    (net (code "5") (name "AD0{slash}SELECTMAP_D7") (class "Default")
      (node (ref "U1") (pin "51") (pinfunction "PA0(AD0)_51") (pintype "bidirectional"))
      (node (ref "U5") (pin "B14") (pinfunction "IO_L5N_T0_D07_14_B14") (pintype "bidirectional"))
    )
    (net (code "6") (name "AD1{slash}SELECTMAP_D6") (class "Default")
      (node (ref "U1") (pin "50") (pinfunction "PA1(AD1)_50") (pintype "bidirectional"))
      (node (ref "U5") (pin "B13") (pinfunction "IO_L5P_T0_D06_14_B13") (pintype "bidirectional"))
    )
    (net (code "7") (name "AD2{slash}SELECTMAP_D5{slash}MCU_RX1") (class "Default")
      (node (ref "J1") (pin "6") (pinfunction "6_6") (pintype "bidirectional"))
      (node (ref "U1") (pin "49") (pinfunction "PA2(AD2)_49") (pintype "bidirectional"))
      (node (ref "U5") (pin "A13") (pinfunction "IO_L4N_T0_D05_14_A13") (pintype "bidirectional"))
    )
    (net (code "8") (name "AD3{slash}SELECTMAP_D4{slash}MCU_TX1") (class "Default")
      (node (ref "J1") (pin "7") (pinfunction "7_7") (pintype "bidirectional"))
      (node (ref "U1") (pin "48") (pinfunction "PA3(AD3)_48") (pintype "bidirectional"))
      (node (ref "U5") (pin "A12") (pinfunction "IO_L4P_T0_D04_14_A12") (pintype "bidirectional"))
    )
    (net (code "9") (name "AD4{slash}SELECTMAP_D3{slash}FPGA_HOLD") (class "Default")
      (node (ref "J1") (pin "8") (pinfunction "8_8") (pintype "bidirectional"))
      (node (ref "U1") (pin "47") (pinfunction "PA4(AD4)_47") (pintype "bidirectional"))
      (node (ref "U5") (pin "C10") (pinfunction "IO_L2N_T0_D03_14_C10") (pintype "bidirectional"))
    )
    (net (code "10") (name "AD5{slash}SELECTMAP_D2{slash}FPGA_WP") (class "Default")
      (node (ref "J1") (pin "5") (pinfunction "5_5") (pintype "bidirectional"))
      (node (ref "U1") (pin "46") (pinfunction "PA5(AD5)_46") (pintype "bidirectional"))
      (node (ref "U5") (pin "D10") (pinfunction "IO_L2P_T0_D02_14_D10") (pintype "bidirectional"))
    )
    (net (code "11") (name "AD6{slash}SELECTMAP_D1{slash}SPI_MISO{slash}MCU_PDO") (class "Default")
      (node (ref "J1") (pin "4") (pinfunction "4_4") (pintype "bidirectional"))
      (node (ref "J3") (pin "1") (pinfunction "MISO_1") (pintype "bidirectional"))
      (node (ref "U1") (pin "13") (pinfunction "(PDO/PCINT3/MISO)PB3_13") (pintype "bidirectional"))
      (node (ref "U1") (pin "45") (pinfunction "PA6(AD6)_45") (pintype "bidirectional"))
      (node (ref "U2") (pin "7") (pinfunction "SDO_7") (pintype "bidirectional"))
      (node (ref "U5") (pin "B12") (pinfunction "IO_L1N_T0_D01_DIN_14_B12") (pintype "bidirectional"))
      (node (ref "U6") (pin "2") (pinfunction "SO_2") (pintype "bidirectional"))
    )
    (net (code "12") (name "AD7{slash}SELECTMAP_D0{slash}SPI_MOSI{slash}PDI") (class "Default")
      (node (ref "J1") (pin "3") (pinfunction "3_3") (pintype "bidirectional"))
      (node (ref "J3") (pin "4") (pinfunction "MOSI_4") (pintype "bidirectional"))
      (node (ref "U1") (pin "12") (pinfunction "(PDI/PCINT2/MOSI)PB2_12") (pintype "bidirectional"))
      (node (ref "U1") (pin "44") (pinfunction "PA7(AD7)_44") (pintype "bidirectional"))
      (node (ref "U2") (pin "5") (pinfunction "SDI_5") (pintype "bidirectional"))
      (node (ref "U5") (pin "B11") (pinfunction "IO_L1P_T0_D00_MOSI_14_B11") (pintype "bidirectional"))
      (node (ref "U6") (pin "5") (pinfunction "SI_5") (pintype "bidirectional"))
    )
    (net (code "13") (name "ALE{slash}HWB") (class "Default")
      (node (ref "J5") (pin "1") (pinfunction "1_1") (pintype "bidirectional"))
      (node (ref "R9") (pin "2") (pinfunction "2_2") (pintype "bidirectional"))
      (node (ref "U1") (pin "43") (pinfunction "PE2(ALE/_HWB)_43") (pintype "bidirectional"))
      (node (ref "U5") (pin "G11") (pinfunction "IO_L12P_T1_MRCC_14_G11") (pintype "bidirectional"))
    )
    (net (code "14") (name "DAUGHTER_VCC") (class "Default")
      (node (ref "J2") (pin "10") (pinfunction "10_10") (pintype "bidirectional"))
      (node (ref "R32") (pin "1") (pinfunction "1_1") (pintype "bidirectional"))
      (node (ref "U8") (pin "2") (pinfunction "SENSE1-_2") (pintype "bidirectional"))
    )
    (net (code "15") (name "EN_OSC_100") (class "Default")
      (node (ref "R23") (pin "1") (pinfunction "1_1") (pintype "bidirectional"))
      (node (ref "U1") (pin "17") (pinfunction "(PCINT7/OC.0A/OC.1C)PB7_17") (pintype "bidirectional"))
      (node (ref "X3") (pin "1") (pinfunction "EN_1") (pintype "bidirectional"))
    )
    (net (code "16") (name "FPGA_AUX_POWER") (class "Default")
      (node (ref "M2") (pin "4") (pinfunction "G_4") (pintype "bidirectional"))
      (node (ref "U1") (pin "18") (pinfunction "(INT4/TOSC1)PE4_18") (pintype "bidirectional"))
    )
    (net (code "17") (name "FPGA_DONE") (class "Default")
      (node (ref "U1") (pin "16") (pinfunction "(PCINT6/OC.1B)PB6_16") (pintype "bidirectional"))
      (node (ref "U5") (pin "P9") (pinfunction "DONE_0_P9") (pintype "bidirectional"))
    )
    (net (code "18") (name "FPGA_GPIO_0") (class "Default")
      (node (ref "J10") (pin "1") (pinfunction "1_1") (pintype "bidirectional"))
      (node (ref "U5") (pin "H14") (pinfunction "IO_L14N_T2_SRCC_14_H14") (pintype "bidirectional"))
    )
    (net (code "19") (name "FPGA_GPIO_1") (class "Default")
      (node (ref "J10") (pin "20") (pinfunction "20_20") (pintype "bidirectional"))
      (node (ref "U5") (pin "H12") (pinfunction "IO_L13N_T2_MRCC_14_H12") (pintype "bidirectional"))
    )
    (net (code "20") (name "FPGA_GPIO_2") (class "Default")
      (node (ref "J10") (pin "2") (pinfunction "2_2") (pintype "bidirectional"))
      (node (ref "U5") (pin "H13") (pinfunction "IO_L14P_T2_SRCC_14_H13") (pintype "bidirectional"))
    )
    (net (code "21") (name "FPGA_GPIO_3") (class "Default")
      (node (ref "J10") (pin "19") (pinfunction "19_19") (pintype "bidirectional"))
      (node (ref "U5") (pin "J13") (pinfunction "IO_L18P_T2_D28_14_J13") (pintype "bidirectional"))
    )
    (net (code "22") (name "FPGA_GPIO_4") (class "Default")
      (node (ref "J10") (pin "3") (pinfunction "3_3") (pintype "bidirectional"))
      (node (ref "U5") (pin "J14") (pinfunction "IO_L18N_T2_D27_14_J14") (pintype "bidirectional"))
    )
    (net (code "23") (name "FPGA_GPIO_5") (class "Default")
      (node (ref "J10") (pin "18") (pinfunction "18_18") (pintype "bidirectional"))
      (node (ref "U5") (pin "J12") (pinfunction "IO_L17N_T2_D29_14_J12") (pintype "bidirectional"))
    )
    (net (code "24") (name "FPGA_GPIO_6") (class "Default")
      (node (ref "J10") (pin "4") (pinfunction "4_4") (pintype "bidirectional"))
      (node (ref "U5") (pin "J11") (pinfunction "IO_L17P_T2_D30_14_J11") (pintype "bidirectional"))
    )
    (net (code "25") (name "FPGA_GPIO_7") (class "Default")
      (node (ref "J10") (pin "17") (pinfunction "17_17") (pintype "bidirectional"))
      (node (ref "U5") (pin "K12") (pinfunction "IO_L19N_T3_D25_VREF_14_K12") (pintype "bidirectional"))
    )
    (net (code "26") (name "FPGA_GPIO_8") (class "Default")
      (node (ref "J10") (pin "5") (pinfunction "5_5") (pintype "bidirectional"))
      (node (ref "U5") (pin "L14") (pinfunction "IO_L15N_T2_DQS_DOUT_CSO_B_14_L14") (pintype "bidirectional"))
    )
    (net (code "27") (name "FPGA_GPIO_9") (class "Default")
      (node (ref "J10") (pin "16") (pinfunction "16_16") (pintype "bidirectional"))
      (node (ref "U5") (pin "L13") (pinfunction "IO_L16N_T2_D31_14_L13") (pintype "bidirectional"))
    )
    (net (code "28") (name "FPGA_GPIO_10") (class "Default")
      (node (ref "J10") (pin "15") (pinfunction "15_15") (pintype "bidirectional"))
      (node (ref "U5") (pin "N14") (pinfunction "IO_L21P_T3_DQS_14_N14") (pintype "bidirectional"))
    )
    (net (code "29") (name "FPGA_GPIO_11") (class "Default")
      (node (ref "J10") (pin "6") (pinfunction "6_6") (pintype "bidirectional"))
      (node (ref "U5") (pin "M14") (pinfunction "IO_L21N_T3_DQS_D22_14_M14") (pintype "bidirectional"))
    )
    (net (code "30") (name "FPGA_GPIO_12") (class "Default")
      (node (ref "J10") (pin "14") (pinfunction "14_14") (pintype "bidirectional"))
      (node (ref "U5") (pin "K11") (pinfunction "IO_L19P_T3_D26_14_K11") (pintype "bidirectional"))
    )
    (net (code "31") (name "FPGA_GPIO_13") (class "Default")
      (node (ref "J10") (pin "7") (pinfunction "7_7") (pintype "bidirectional"))
      (node (ref "U5") (pin "P13") (pinfunction "IO_L22N_T3_D20_14_P13") (pintype "bidirectional"))
    )
    (net (code "32") (name "FPGA_GPIO_14") (class "Default")
      (node (ref "J10") (pin "8") (pinfunction "8_8") (pintype "bidirectional"))
      (node (ref "U5") (pin "M12") (pinfunction "IO_L20N_T3_D23_14_M12") (pintype "bidirectional"))
    )
    (net (code "33") (name "FPGA_GPIO_15") (class "Default")
      (node (ref "J10") (pin "13") (pinfunction "13_13") (pintype "bidirectional"))
      (node (ref "U5") (pin "P12") (pinfunction "IO_L22P_T3_D21_14_P12") (pintype "bidirectional"))
    )
    (net (code "34") (name "FPGA_GPIO_16") (class "Default")
      (node (ref "J10") (pin "9") (pinfunction "9_9") (pintype "bidirectional"))
      (node (ref "U5") (pin "N11") (pinfunction "IO_L23N_T3_D18_14_N11") (pintype "bidirectional"))
    )
    (net (code "35") (name "FPGA_GPIO_17") (class "Default")
      (node (ref "J10") (pin "12") (pinfunction "12_12") (pintype "bidirectional"))
      (node (ref "U5") (pin "P11") (pinfunction "IO_L24N_T3_D16_14_P11") (pintype "bidirectional"))
    )
    (net (code "36") (name "FPGA_GPIO_18") (class "Default")
      (node (ref "J10") (pin "10") (pinfunction "10_10") (pintype "bidirectional"))
      (node (ref "U5") (pin "N10") (pinfunction "IO_L23P_T3_D19_14_N10") (pintype "bidirectional"))
    )
    (net (code "37") (name "FPGA_GPIO_19") (class "Default")
      (node (ref "J10") (pin "11") (pinfunction "11_11") (pintype "bidirectional"))
      (node (ref "U5") (pin "P10") (pinfunction "IO_L24P_T3_D17_14_P10") (pintype "bidirectional"))
    )
    (net (code "38") (name "FPGA_INT_POWER") (class "Default")
      (node (ref "M1") (pin "4") (pinfunction "G_4") (pintype "bidirectional"))
      (node (ref "U1") (pin "10") (pinfunction "(SS/PCINT0)PB0_10") (pintype "bidirectional"))
    )
    (net (code "39") (name "FPGA_IO_POWER") (class "Default")
      (node (ref "M3") (pin "4") (pinfunction "G_4") (pintype "bidirectional"))
      (node (ref "U1") (pin "2") (pinfunction "(INT.7/AIN.1/UVCON)PE7_2") (pintype "bidirectional"))
    )
    (net (code "40") (name "FPGA_LED0") (class "Default")
      (node (ref "R18") (pin "1") (pinfunction "1_1") (pintype "bidirectional"))
      (node (ref "U5") (pin "E11") (pinfunction "IO_0_14_E11") (pintype "bidirectional"))
    )
    (net (code "41") (name "FPGA_LED1") (class "Default")
      (node (ref "R19") (pin "1") (pinfunction "1_1") (pintype "bidirectional"))
      (node (ref "U5") (pin "B10") (pinfunction "IO_L3P_T0_DQS_PUDC_B_14_B10") (pintype "bidirectional"))
    )
    (net (code "42") (name "FPGA_LED2") (class "Default")
      (node (ref "R20") (pin "1") (pinfunction "1_1") (pintype "bidirectional"))
      (node (ref "U5") (pin "C12") (pinfunction "IO_L6N_T0_D08_VREF_14_C12") (pintype "bidirectional"))
    )
    (net (code "43") (name "FPGA_LED3") (class "Default")
      (node (ref "R22") (pin "1") (pinfunction "1_1") (pintype "bidirectional"))
      (node (ref "U5") (pin "M11") (pinfunction "IO_L20P_T3_D24_14_M11") (pintype "bidirectional"))
    )
    (net (code "44") (name "FPGA_RESET") (class "Default")
      (node (ref "R28") (pin "1") (pinfunction "1_1") (pintype "bidirectional"))
      (node (ref "S3") (pin "2") (pinfunction "3_2") (pintype "bidirectional"))
      (node (ref "U1") (pin "59") (pinfunction "PF2(ADC2)_59") (pintype "bidirectional"))
      (node (ref "U5") (pin "L7") (pinfunction "PROGRAM_B_0_L7") (pintype "bidirectional"))
    )
    (net (code "45") (name "FPGA_VCCAUX") (class "Default")
      (node (ref "C12") (pin "1") (pinfunction "P$1_1") (pintype "bidirectional"))
      (node (ref "C13") (pin "1") (pinfunction "P$1_1") (pintype "bidirectional"))
      (node (ref "C14") (pin "1") (pinfunction "P$1_1") (pintype "bidirectional"))
      (node (ref "C15") (pin "1") (pinfunction "P$1_1") (pintype "bidirectional"))
      (node (ref "C16") (pin "1") (pinfunction "P$1_1") (pintype "bidirectional"))
      (node (ref "M2") (pin "5") (pinfunction "D_5") (pintype "bidirectional"))
      (node (ref "M2") (pin "6") (pinfunction "D_6") (pintype "bidirectional"))
      (node (ref "M2") (pin "7") (pinfunction "D_7") (pintype "bidirectional"))
      (node (ref "M2") (pin "8") (pinfunction "D_8") (pintype "bidirectional"))
      (node (ref "U5") (pin "F10") (pinfunction "VCCAUX_F10") (pintype "bidirectional"))
      (node (ref "U5") (pin "H10") (pinfunction "VCCAUX_H10") (pintype "bidirectional"))
      (node (ref "U5") (pin "K10") (pinfunction "VCCAUX_K10") (pintype "bidirectional"))
      (node (ref "U5") (pin "L9") (pinfunction "VCCAUX_L9") (pintype "bidirectional"))
      (node (ref "U5") (pin "N7") (pinfunction "CFGBVS_0_N7") (pintype "bidirectional"))
    )
    (net (code "46") (name "FPGA_VCCAUX_MON") (class "Default")
      (node (ref "M2") (pin "1") (pinfunction "S_1") (pintype "bidirectional"))
      (node (ref "M2") (pin "2") (pinfunction "S_2") (pintype "bidirectional"))
      (node (ref "M2") (pin "3") (pinfunction "S_3") (pintype "bidirectional"))
      (node (ref "R38") (pin "1") (pinfunction "1_1") (pintype "bidirectional"))
      (node (ref "U10") (pin "2") (pinfunction "SENSE1-_2") (pintype "bidirectional"))
    )
    (net (code "47") (name "FPGA_VCCINT") (class "Default")
      (node (ref "C10") (pin "1") (pinfunction "P$1_1") (pintype "bidirectional"))
      (node (ref "C11") (pin "1") (pinfunction "P$1_1") (pintype "bidirectional"))
      (node (ref "C7") (pin "1") (pinfunction "P$1_1") (pintype "bidirectional"))
      (node (ref "C8") (pin "1") (pinfunction "P$1_1") (pintype "bidirectional"))
      (node (ref "C9") (pin "1") (pinfunction "P$1_1") (pintype "bidirectional"))
      (node (ref "M1") (pin "5") (pinfunction "D_5") (pintype "bidirectional"))
      (node (ref "M1") (pin "6") (pinfunction "D_6") (pintype "bidirectional"))
      (node (ref "M1") (pin "7") (pinfunction "D_7") (pintype "bidirectional"))
      (node (ref "M1") (pin "8") (pinfunction "D_8") (pintype "bidirectional"))
      (node (ref "U5") (pin "D6") (pinfunction "VCCINT_D6") (pintype "bidirectional"))
      (node (ref "U5") (pin "D8") (pinfunction "VCCINT_D8") (pintype "bidirectional"))
      (node (ref "U5") (pin "E5") (pinfunction "VCCBRAM_E5") (pintype "bidirectional"))
      (node (ref "U5") (pin "E7") (pinfunction "VCCINT_E7") (pintype "bidirectional"))
      (node (ref "U5") (pin "E9") (pinfunction "VCCINT_E9") (pintype "bidirectional"))
      (node (ref "U5") (pin "F6") (pinfunction "VCCINT_F6") (pintype "bidirectional"))
      (node (ref "U5") (pin "G5") (pinfunction "VCCBRAM_G5") (pintype "bidirectional"))
      (node (ref "U5") (pin "G9") (pinfunction "VCCINT_G9") (pintype "bidirectional"))
      (node (ref "U5") (pin "H6") (pinfunction "VCCINT_H6") (pintype "bidirectional"))
      (node (ref "U5") (pin "J5") (pinfunction "VCCBRAM_J5") (pintype "bidirectional"))
      (node (ref "U5") (pin "J9") (pinfunction "VCCINT_J9") (pintype "bidirectional"))
      (node (ref "U5") (pin "K6") (pinfunction "VCCINT_K6") (pintype "bidirectional"))
      (node (ref "U5") (pin "K8") (pinfunction "VCCINT_K8") (pintype "bidirectional"))
    )
    (net (code "48") (name "FPGA_VCCINT_MON") (class "Default")
      (node (ref "M1") (pin "1") (pinfunction "S_1") (pintype "bidirectional"))
      (node (ref "M1") (pin "2") (pinfunction "S_2") (pintype "bidirectional"))
      (node (ref "M1") (pin "3") (pinfunction "S_3") (pintype "bidirectional"))
      (node (ref "R40") (pin "1") (pinfunction "1_1") (pintype "bidirectional"))
      (node (ref "U10") (pin "4") (pinfunction "SENSE2-_4") (pintype "bidirectional"))
    )
    (net (code "49") (name "FPGA_VCCIO") (class "Default")
      (node (ref "C17") (pin "1") (pinfunction "P$1_1") (pintype "bidirectional"))
      (node (ref "C18") (pin "1") (pinfunction "P$1_1") (pintype "bidirectional"))
      (node (ref "C19") (pin "1") (pinfunction "P$1_1") (pintype "bidirectional"))
      (node (ref "C20") (pin "1") (pinfunction "P$1_1") (pintype "bidirectional"))
      (node (ref "C21") (pin "1") (pinfunction "P$1_1") (pintype "bidirectional"))
      (node (ref "C22") (pin "1") (pinfunction "P$1_1") (pintype "bidirectional"))
      (node (ref "C23") (pin "1") (pinfunction "P$1_1") (pintype "bidirectional"))
      (node (ref "J9") (pin "1") (pinfunction "REF_1") (pintype "bidirectional"))
      (node (ref "M3") (pin "5") (pinfunction "D_5") (pintype "bidirectional"))
      (node (ref "M3") (pin "6") (pinfunction "D_6") (pintype "bidirectional"))
      (node (ref "M3") (pin "7") (pinfunction "D_7") (pintype "bidirectional"))
      (node (ref "M3") (pin "8") (pinfunction "D_8") (pintype "bidirectional"))
      (node (ref "R21") (pin "2") (pinfunction "2_2") (pintype "bidirectional"))
      (node (ref "R23") (pin "2") (pinfunction "2_2") (pintype "bidirectional"))
      (node (ref "R24") (pin "1") (pinfunction "1_1") (pintype "bidirectional"))
      (node (ref "R25") (pin "1") (pinfunction "1_1") (pintype "bidirectional"))
      (node (ref "R26") (pin "1") (pinfunction "1_1") (pintype "bidirectional"))
      (node (ref "R28") (pin "2") (pinfunction "2_2") (pintype "bidirectional"))
      (node (ref "U5") (pin "G13") (pinfunction "VCCO_14_G13") (pintype "bidirectional"))
      (node (ref "U5") (pin "K13") (pinfunction "VCCO_14_K13") (pintype "bidirectional"))
      (node (ref "U5") (pin "N13") (pinfunction "VCCO_14_N13") (pintype "bidirectional"))
      (node (ref "U5") (pin "N6") (pinfunction "VCCO_0_N6") (pintype "bidirectional"))
      (node (ref "U5") (pin "N8") (pinfunction "VCCO_0_N8") (pintype "bidirectional"))
      (node (ref "X3") (pin "4") (pinfunction "VS+_4") (pintype "bidirectional"))
      (node (ref "X4") (pin "1") (pinfunction "EN_1") (pintype "bidirectional"))
      (node (ref "X4") (pin "4") (pinfunction "VS+_4") (pintype "bidirectional"))
      (node (ref "X5") (pin "1") (pinfunction "EN_1") (pintype "bidirectional"))
      (node (ref "X5") (pin "4") (pinfunction "VS+_4") (pintype "bidirectional"))
    )
    (net (code "50") (name "FPGA_VCCIO_MON") (class "Default")
      (node (ref "M3") (pin "1") (pinfunction "S_1") (pintype "bidirectional"))
      (node (ref "M3") (pin "2") (pinfunction "S_2") (pintype "bidirectional"))
      (node (ref "M3") (pin "3") (pinfunction "S_3") (pintype "bidirectional"))
      (node (ref "R33") (pin "1") (pinfunction "1_1") (pintype "bidirectional"))
      (node (ref "U7") (pin "4") (pinfunction "SENSE2-_4") (pintype "bidirectional"))
    )
    (net (code "51") (name "GND") (class "Default")
      (node (ref "C1") (pin "2") (pinfunction "P$2_2") (pintype "bidirectional"))
      (node (ref "C10") (pin "2") (pinfunction "P$2_2") (pintype "bidirectional"))
      (node (ref "C11") (pin "2") (pinfunction "P$2_2") (pintype "bidirectional"))
      (node (ref "C12") (pin "2") (pinfunction "P$2_2") (pintype "bidirectional"))
      (node (ref "C13") (pin "2") (pinfunction "P$2_2") (pintype "bidirectional"))
      (node (ref "C14") (pin "2") (pinfunction "P$2_2") (pintype "bidirectional"))
      (node (ref "C15") (pin "2") (pinfunction "P$2_2") (pintype "bidirectional"))
      (node (ref "C16") (pin "2") (pinfunction "P$2_2") (pintype "bidirectional"))
      (node (ref "C17") (pin "2") (pinfunction "P$2_2") (pintype "bidirectional"))
      (node (ref "C18") (pin "2") (pinfunction "P$2_2") (pintype "bidirectional"))
      (node (ref "C19") (pin "2") (pinfunction "P$2_2") (pintype "bidirectional"))
      (node (ref "C2") (pin "2") (pinfunction "P$2_2") (pintype "bidirectional"))
      (node (ref "C20") (pin "2") (pinfunction "P$2_2") (pintype "bidirectional"))
      (node (ref "C21") (pin "2") (pinfunction "P$2_2") (pintype "bidirectional"))
      (node (ref "C22") (pin "2") (pinfunction "P$2_2") (pintype "bidirectional"))
      (node (ref "C23") (pin "2") (pinfunction "P$2_2") (pintype "bidirectional"))
      (node (ref "C24") (pin "2") (pinfunction "P$2_2") (pintype "bidirectional"))
      (node (ref "C25") (pin "2") (pinfunction "P$2_2") (pintype "bidirectional"))
      (node (ref "C26") (pin "2") (pinfunction "P$2_2") (pintype "bidirectional"))
      (node (ref "C27") (pin "2") (pinfunction "P$2_2") (pintype "bidirectional"))
      (node (ref "C28") (pin "2") (pinfunction "P$2_2") (pintype "bidirectional"))
      (node (ref "C29") (pin "2") (pinfunction "P$2_2") (pintype "bidirectional"))
      (node (ref "C3") (pin "2") (pinfunction "P$2_2") (pintype "bidirectional"))
      (node (ref "C30") (pin "2") (pinfunction "P$2_2") (pintype "bidirectional"))
      (node (ref "C31") (pin "2") (pinfunction "P$2_2") (pintype "bidirectional"))
      (node (ref "C32") (pin "2") (pinfunction "P$2_2") (pintype "bidirectional"))
      (node (ref "C33") (pin "2") (pinfunction "P$2_2") (pintype "bidirectional"))
      (node (ref "C34") (pin "2") (pinfunction "P$2_2") (pintype "bidirectional"))
      (node (ref "C35") (pin "1") (pinfunction "P$1_1") (pintype "bidirectional"))
      (node (ref "C4") (pin "2") (pinfunction "P$2_2") (pintype "bidirectional"))
      (node (ref "C5") (pin "2") (pinfunction "P$2_2") (pintype "bidirectional"))
      (node (ref "C6") (pin "2") (pinfunction "P$2_2") (pintype "bidirectional"))
      (node (ref "C7") (pin "2") (pinfunction "P$2_2") (pintype "bidirectional"))
      (node (ref "C8") (pin "2") (pinfunction "P$2_2") (pintype "bidirectional"))
      (node (ref "C9") (pin "2") (pinfunction "P$2_2") (pintype "bidirectional"))
      (node (ref "D1") (pin "2") (pinfunction "2_2") (pintype "bidirectional"))
      (node (ref "D10") (pin "2") (pinfunction "2_2") (pintype "bidirectional"))
      (node (ref "D2") (pin "2") (pinfunction "2_2") (pintype "bidirectional"))
      (node (ref "D3") (pin "2") (pinfunction "2_2") (pintype "bidirectional"))
      (node (ref "D4") (pin "2") (pinfunction "2_2") (pintype "bidirectional"))
      (node (ref "D5") (pin "2") (pinfunction "2_2") (pintype "bidirectional"))
      (node (ref "D6") (pin "2") (pinfunction "2_2") (pintype "bidirectional"))
      (node (ref "D7") (pin "2") (pinfunction "2_2") (pintype "bidirectional"))
      (node (ref "D8") (pin "2") (pinfunction "2_2") (pintype "bidirectional"))
      (node (ref "D9") (pin "2") (pinfunction "2_2") (pintype "bidirectional"))
      (node (ref "J11") (pin "5") (pinfunction "GND_5") (pintype "bidirectional"))
      (node (ref "J2") (pin "7") (pinfunction "7_7") (pintype "bidirectional"))
      (node (ref "J2") (pin "8") (pinfunction "8_8") (pintype "bidirectional"))
      (node (ref "J3") (pin "6") (pinfunction "GND_6") (pintype "bidirectional"))
      (node (ref "J5") (pin "2") (pinfunction "2_2") (pintype "bidirectional"))
      (node (ref "J6") (pin "6") (pinfunction "GND_6") (pintype "bidirectional"))
      (node (ref "J7") (pin "2") (pinfunction "2_2") (pintype "bidirectional"))
      (node (ref "J8") (pin "5") (pinfunction "GND_5") (pintype "bidirectional"))
      (node (ref "J9") (pin "2") (pinfunction "GND_2") (pintype "bidirectional"))
      (node (ref "R35") (pin "1") (pinfunction "1_1") (pintype "bidirectional"))
      (node (ref "R36") (pin "1") (pinfunction "1_1") (pintype "bidirectional"))
      (node (ref "R41") (pin "1") (pinfunction "1_1") (pintype "bidirectional"))
      (node (ref "R42") (pin "1") (pinfunction "1_1") (pintype "bidirectional"))
      (node (ref "R46") (pin "2") (pinfunction "2_2") (pintype "bidirectional"))
      (node (ref "R47") (pin "2") (pinfunction "2_2") (pintype "bidirectional"))
      (node (ref "R48") (pin "1") (pinfunction "1_1") (pintype "bidirectional"))
      (node (ref "R49") (pin "1") (pinfunction "1_1") (pintype "bidirectional"))
      (node (ref "S1") (pin "1") (pinfunction "1_1") (pintype "bidirectional"))
      (node (ref "S2") (pin "5") (pinfunction "4Y_5") (pintype "bidirectional"))
      (node (ref "S2") (pin "6") (pinfunction "3Y_6") (pintype "bidirectional"))
      (node (ref "S2") (pin "7") (pinfunction "2Y_7") (pintype "bidirectional"))
      (node (ref "S2") (pin "8") (pinfunction "1Y_8") (pintype "bidirectional"))
      (node (ref "S3") (pin "1") (pinfunction "1_1") (pintype "bidirectional"))
      (node (ref "TP5") (pin "3") (pinfunction ">NAME_3") (pintype "bidirectional"))
      (node (ref "U1") (pin "22") (pinfunction "GND_22") (pintype "bidirectional"))
      (node (ref "U1") (pin "53") (pinfunction "GND_53") (pintype "bidirectional"))
      (node (ref "U1") (pin "6") (pinfunction "UGND_6") (pintype "bidirectional"))
      (node (ref "U1") (pin "63") (pinfunction "GND_63") (pintype "bidirectional"))
      (node (ref "U1") (pin "PAD") (pinfunction "GND_PAD") (pintype "bidirectional"))
      (node (ref "U1") (pin "VIA1") (pinfunction "GND_VIA1") (pintype "bidirectional"))
      (node (ref "U1") (pin "VIA2") (pinfunction "GND_VIA2") (pintype "bidirectional"))
      (node (ref "U1") (pin "VIA3") (pinfunction "GND_VIA3") (pintype "bidirectional"))
      (node (ref "U1") (pin "VIA4") (pinfunction "GND_VIA4") (pintype "bidirectional"))
      (node (ref "U1") (pin "VIA5") (pinfunction "GND_VIA5") (pintype "bidirectional"))
      (node (ref "U1") (pin "VIA6") (pinfunction "GND_VIA6") (pintype "bidirectional"))
      (node (ref "U1") (pin "VIA7") (pinfunction "GND_VIA7") (pintype "bidirectional"))
      (node (ref "U1") (pin "VIA8") (pinfunction "GND_VIA8") (pintype "bidirectional"))
      (node (ref "U1") (pin "VIA9") (pinfunction "GND_VIA9") (pintype "bidirectional"))
      (node (ref "U10") (pin "5") (pinfunction "GND_5") (pintype "bidirectional"))
      (node (ref "U10") (pin "P$1") (pinfunction "GND_P$1") (pintype "bidirectional"))
      (node (ref "U10") (pin "P$2") (pinfunction "GND_P$2") (pintype "bidirectional"))
      (node (ref "U10") (pin "P$3") (pinfunction "GND_P$3") (pintype "bidirectional"))
      (node (ref "U10") (pin "P$4") (pinfunction "GND_P$4") (pintype "bidirectional"))
      (node (ref "U11") (pin "9") (pinfunction "GND_9") (pintype "bidirectional"))
      (node (ref "U12") (pin "9") (pinfunction "GND_9") (pintype "bidirectional"))
      (node (ref "U2") (pin "1") (pinfunction "GND_1") (pintype "bidirectional"))
      (node (ref "U2") (pin "11") (pinfunction "GND_11") (pintype "bidirectional"))
      (node (ref "U2") (pin "12") (pinfunction "GND_12") (pintype "bidirectional"))
      (node (ref "U3") (pin "15") (pinfunction "GND_15") (pintype "bidirectional"))
      (node (ref "U3") (pin "23") (pinfunction "GND_23") (pintype "bidirectional"))
      (node (ref "U3") (pin "35") (pinfunction "GND_35") (pintype "bidirectional"))
      (node (ref "U3") (pin "43") (pinfunction "GND_43") (pintype "bidirectional"))
      (node (ref "U3") (pin "45") (pinfunction "GND_45") (pintype "bidirectional"))
      (node (ref "U3") (pin "5") (pinfunction "UGND_5") (pintype "bidirectional"))
      (node (ref "U4") (pin "12") (pinfunction "GND_12") (pintype "bidirectional"))
      (node (ref "U4") (pin "34") (pinfunction "GND_34") (pintype "bidirectional"))
      (node (ref "U5") (pin "A1") (pinfunction "GND_A1") (pintype "bidirectional"))
      (node (ref "U5") (pin "A11") (pinfunction "GND_A11") (pintype "bidirectional"))
      (node (ref "U5") (pin "A14") (pinfunction "GND_A14") (pintype "bidirectional"))
      (node (ref "U5") (pin "A6") (pinfunction "GND_A6") (pintype "bidirectional"))
      (node (ref "U5") (pin "A9") (pinfunction "GND_A9") (pintype "bidirectional"))
      (node (ref "U5") (pin "B4") (pinfunction "GND_B4") (pintype "bidirectional"))
      (node (ref "U5") (pin "B7") (pinfunction "GND_B7") (pintype "bidirectional"))
      (node (ref "U5") (pin "B9") (pinfunction "GND_B9") (pintype "bidirectional"))
      (node (ref "U5") (pin "C13") (pinfunction "GND_C13") (pintype "bidirectional"))
      (node (ref "U5") (pin "C2") (pinfunction "GND_C2") (pintype "bidirectional"))
      (node (ref "U5") (pin "C6") (pinfunction "GND_C6") (pintype "bidirectional"))
      (node (ref "U5") (pin "C7") (pinfunction "GND_C7") (pintype "bidirectional"))
      (node (ref "U5") (pin "C8") (pinfunction "GND_C8") (pintype "bidirectional"))
      (node (ref "U5") (pin "C9") (pinfunction "GND_C9") (pintype "bidirectional"))
      (node (ref "U5") (pin "D11") (pinfunction "GND_D11") (pintype "bidirectional"))
      (node (ref "U5") (pin "D5") (pinfunction "GND_D5") (pintype "bidirectional"))
      (node (ref "U5") (pin "D7") (pinfunction "GND_D7") (pintype "bidirectional"))
      (node (ref "U5") (pin "D9") (pinfunction "GND_D9") (pintype "bidirectional"))
      (node (ref "U5") (pin "E1") (pinfunction "GND_E1") (pintype "bidirectional"))
      (node (ref "U5") (pin "E10") (pinfunction "GND_E10") (pintype "bidirectional"))
      (node (ref "U5") (pin "E14") (pinfunction "GND_E14") (pintype "bidirectional"))
      (node (ref "U5") (pin "E3") (pinfunction "GND_E3") (pintype "bidirectional"))
      (node (ref "U5") (pin "E6") (pinfunction "GND_E6") (pintype "bidirectional"))
      (node (ref "U5") (pin "E8") (pinfunction "GND_E8") (pintype "bidirectional"))
      (node (ref "U5") (pin "F5") (pinfunction "GND_F5") (pintype "bidirectional"))
      (node (ref "U5") (pin "F9") (pinfunction "GND_F9") (pintype "bidirectional"))
      (node (ref "U5") (pin "G10") (pinfunction "GND_G10") (pintype "bidirectional"))
      (node (ref "U5") (pin "G12") (pinfunction "GND_G12") (pintype "bidirectional"))
      (node (ref "U5") (pin "G3") (pinfunction "GND_G3") (pintype "bidirectional"))
      (node (ref "U5") (pin "G6") (pinfunction "GND_G6") (pintype "bidirectional"))
      (node (ref "U5") (pin "H5") (pinfunction "GND_H5") (pintype "bidirectional"))
      (node (ref "U5") (pin "H9") (pinfunction "GND_H9") (pintype "bidirectional"))
      (node (ref "U5") (pin "J10") (pinfunction "GND_J10") (pintype "bidirectional"))
      (node (ref "U5") (pin "J6") (pinfunction "GND_J6") (pintype "bidirectional"))
      (node (ref "U5") (pin "J7") (pinfunction "DXN_0_J7") (pintype "bidirectional"))
      (node (ref "U5") (pin "J8") (pinfunction "DXP_0_J8") (pintype "bidirectional"))
      (node (ref "U5") (pin "K1") (pinfunction "GND_K1") (pintype "bidirectional"))
      (node (ref "U5") (pin "K14") (pinfunction "GND_K14") (pintype "bidirectional"))
      (node (ref "U5") (pin "K5") (pinfunction "GND_K5") (pintype "bidirectional"))
      (node (ref "U5") (pin "K7") (pinfunction "GND_K7") (pintype "bidirectional"))
      (node (ref "U5") (pin "K9") (pinfunction "GND_K9") (pintype "bidirectional"))
      (node (ref "U5") (pin "L10") (pinfunction "GND_L10") (pintype "bidirectional"))
      (node (ref "U5") (pin "L11") (pinfunction "GND_L11") (pintype "bidirectional"))
      (node (ref "U5") (pin "L12") (pinfunction "IO_L16P_T2_CSI_B_14_L12") (pintype "bidirectional"))
      (node (ref "U5") (pin "L4") (pinfunction "GND_L4") (pintype "bidirectional"))
      (node (ref "U5") (pin "L6") (pinfunction "GND_L6") (pintype "bidirectional"))
      (node (ref "U5") (pin "L8") (pinfunction "GND_L8") (pintype "bidirectional"))
      (node (ref "U5") (pin "M13") (pinfunction "IO_L15P_T2_DQS_RDWR_B_14_M13") (pintype "bidirectional"))
      (node (ref "U5") (pin "N12") (pinfunction "GND_N12") (pintype "bidirectional"))
      (node (ref "U5") (pin "N3") (pinfunction "GND_N3") (pintype "bidirectional"))
      (node (ref "U5") (pin "N5") (pinfunction "GND_N5") (pintype "bidirectional"))
      (node (ref "U5") (pin "N9") (pinfunction "GND_N9") (pintype "bidirectional"))
      (node (ref "U5") (pin "P1") (pinfunction "GND_P1") (pintype "bidirectional"))
      (node (ref "U5") (pin "P14") (pinfunction "GND_P14") (pintype "bidirectional"))
      (node (ref "U6") (pin "4") (pinfunction "VSS_4") (pintype "bidirectional"))
      (node (ref "U7") (pin "5") (pinfunction "GND_5") (pintype "bidirectional"))
      (node (ref "U7") (pin "P$1") (pinfunction "GND_P$1") (pintype "bidirectional"))
      (node (ref "U7") (pin "P$2") (pinfunction "GND_P$2") (pintype "bidirectional"))
      (node (ref "U7") (pin "P$3") (pinfunction "GND_P$3") (pintype "bidirectional"))
      (node (ref "U7") (pin "P$4") (pinfunction "GND_P$4") (pintype "bidirectional"))
      (node (ref "U8") (pin "5") (pinfunction "GND_5") (pintype "bidirectional"))
      (node (ref "U8") (pin "P$1") (pinfunction "GND_P$1") (pintype "bidirectional"))
      (node (ref "U8") (pin "P$2") (pinfunction "GND_P$2") (pintype "bidirectional"))
      (node (ref "U8") (pin "P$3") (pinfunction "GND_P$3") (pintype "bidirectional"))
      (node (ref "U8") (pin "P$4") (pinfunction "GND_P$4") (pintype "bidirectional"))
      (node (ref "U9") (pin "5") (pinfunction "GND_5") (pintype "bidirectional"))
      (node (ref "U9") (pin "P$1") (pinfunction "GND_P$1") (pintype "bidirectional"))
      (node (ref "U9") (pin "P$2") (pinfunction "GND_P$2") (pintype "bidirectional"))
      (node (ref "U9") (pin "P$3") (pinfunction "GND_P$3") (pintype "bidirectional"))
      (node (ref "U9") (pin "P$4") (pinfunction "GND_P$4") (pintype "bidirectional"))
      (node (ref "X3") (pin "2") (pinfunction "GND_2") (pintype "bidirectional"))
      (node (ref "X4") (pin "2") (pinfunction "GND_2") (pintype "bidirectional"))
      (node (ref "X5") (pin "2") (pinfunction "GND_2") (pintype "bidirectional"))
    )
    (net (code "52") (name "INIT_B") (class "Default")
      (node (ref "R21") (pin "1") (pinfunction "1_1") (pintype "bidirectional"))
      (node (ref "U1") (pin "58") (pinfunction "PF3(ADC3)_58") (pintype "bidirectional"))
      (node (ref "U5") (pin "P8") (pinfunction "INIT_B_0_P8") (pintype "bidirectional"))
    )
    (net (code "53") (name "JTAG_TCK") (class "Default")
      (node (ref "J9") (pin "3") (pinfunction "TCK_3") (pintype "bidirectional"))
      (node (ref "U1") (pin "57") (pinfunction "PF4(ADC4/TCK)_57") (pintype "bidirectional"))
      (node (ref "U5") (pin "A7") (pinfunction "TCK_0_A7") (pintype "bidirectional"))
    )
    (net (code "54") (name "JTAG_TDI") (class "Default")
      (node (ref "J9") (pin "5") (pinfunction "TDI_5") (pintype "bidirectional"))
      (node (ref "U1") (pin "54") (pinfunction "PF7(ADC7/TDI)_54") (pintype "bidirectional"))
      (node (ref "U5") (pin "P7") (pinfunction "TDI_0_P7") (pintype "bidirectional"))
    )
    (net (code "55") (name "JTAG_TDO") (class "Default")
      (node (ref "J9") (pin "4") (pinfunction "TDO_4") (pintype "bidirectional"))
      (node (ref "U1") (pin "55") (pinfunction "PF6(ADC6/TDO)_55") (pintype "bidirectional"))
      (node (ref "U5") (pin "P6") (pinfunction "TDO_0_P6") (pintype "bidirectional"))
    )
    (net (code "56") (name "JTAG_TMS") (class "Default")
      (node (ref "J9") (pin "6") (pinfunction "TMS_6") (pintype "bidirectional"))
      (node (ref "U1") (pin "56") (pinfunction "PF5(ADC5/TMS)_56") (pintype "bidirectional"))
      (node (ref "U5") (pin "M6") (pinfunction "TMS_0_M6") (pintype "bidirectional"))
    )
    (net (code "57") (name "MCU_LED0") (class "Default")
      (node (ref "R1") (pin "1") (pinfunction "1_1") (pintype "bidirectional"))
      (node (ref "U1") (pin "32") (pinfunction "(T0)PD7_32") (pintype "bidirectional"))
    )
    (net (code "58") (name "MCU_LED1") (class "Default")
      (node (ref "R2") (pin "1") (pinfunction "1_1") (pintype "bidirectional"))
      (node (ref "U1") (pin "31") (pinfunction "(T1)PD6_31") (pintype "bidirectional"))
    )
    (net (code "59") (name "MCU_LED2") (class "Default")
      (node (ref "R3") (pin "1") (pinfunction "1_1") (pintype "bidirectional"))
      (node (ref "U1") (pin "30") (pinfunction "(XCK1)PD5_30") (pintype "bidirectional"))
    )
    (net (code "60") (name "MCU_LED3") (class "Default")
      (node (ref "R4") (pin "1") (pinfunction "1_1") (pintype "bidirectional"))
      (node (ref "U1") (pin "29") (pinfunction "(ICP1)PD4_29") (pintype "bidirectional"))
    )
    (net (code "61") (name "MCU_RESET") (class "Default")
      (node (ref "J3") (pin "5") (pinfunction "RST_5") (pintype "bidirectional"))
      (node (ref "R8") (pin "1") (pinfunction "1_1") (pintype "bidirectional"))
      (node (ref "S1") (pin "2") (pinfunction "3_2") (pintype "bidirectional"))
      (node (ref "U1") (pin "20") (pinfunction "_RESET_20") (pintype "bidirectional"))
    )
    (net (code "62") (name "MCU_RX") (class "Default")
      (node (ref "J4") (pin "3") (pinfunction "2_3") (pintype "bidirectional"))
      (node (ref "U1") (pin "27") (pinfunction "(RXD1/INT2)PD2_27") (pintype "bidirectional"))
    )
    (net (code "63") (name "MCU_TX") (class "Default")
      (node (ref "J4") (pin "1") (pinfunction "1_1") (pintype "bidirectional"))
      (node (ref "U1") (pin "28") (pinfunction "(TXD1/INT3)PD3_28") (pintype "bidirectional"))
    )
    (net (code "64") (name "MCU_VCC") (class "Default")
      (node (ref "C1") (pin "1") (pinfunction "P$1_1") (pintype "bidirectional"))
      (node (ref "R34") (pin "1") (pinfunction "1_1") (pintype "bidirectional"))
      (node (ref "R7") (pin "1") (pinfunction "1_1") (pintype "bidirectional"))
      (node (ref "R8") (pin "2") (pinfunction "2_2") (pintype "bidirectional"))
      (node (ref "R9") (pin "1") (pinfunction "1_1") (pintype "bidirectional"))
      (node (ref "U1") (pin "21") (pinfunction "UVCC_21") (pintype "bidirectional"))
      (node (ref "U1") (pin "3") (pinfunction "UVCC_3") (pintype "bidirectional"))
      (node (ref "U1") (pin "52") (pinfunction "VCC_52") (pintype "bidirectional"))
      (node (ref "U1") (pin "62") (pinfunction "AREF_62") (pintype "bidirectional"))
      (node (ref "U1") (pin "64") (pinfunction "AVCC_64") (pintype "bidirectional"))
      (node (ref "U1") (pin "7") (pinfunction "UCAP_7") (pintype "bidirectional"))
      (node (ref "U8") (pin "4") (pinfunction "SENSE2-_4") (pintype "bidirectional"))
    )
    (net (code "65") (name "MODE0") (class "Default")
      (node (ref "R24") (pin "2") (pinfunction "2_2") (pintype "bidirectional"))
      (node (ref "S2") (pin "1") (pinfunction "1X_1") (pintype "bidirectional"))
      (node (ref "U5") (pin "M7") (pinfunction "M0_0_M7") (pintype "bidirectional"))
    )
    (net (code "66") (name "MODE1") (class "Default")
      (node (ref "R25") (pin "2") (pinfunction "2_2") (pintype "bidirectional"))
      (node (ref "S2") (pin "2") (pinfunction "2X_2") (pintype "bidirectional"))
      (node (ref "U5") (pin "M8") (pinfunction "M1_0_M8") (pintype "bidirectional"))
    )
    (net (code "67") (name "MODE2") (class "Default")
      (node (ref "R26") (pin "2") (pinfunction "2_2") (pintype "bidirectional"))
      (node (ref "S2") (pin "3") (pinfunction "3X_3") (pintype "bidirectional"))
      (node (ref "U5") (pin "M9") (pinfunction "M2_0_M9") (pintype "bidirectional"))
    )
    (net (code "68") (name "MONITORING") (class "Default")
      (node (ref "R16") (pin "2") (pinfunction "2_2") (pintype "bidirectional"))
      (node (ref "S2") (pin "4") (pinfunction "4X_4") (pintype "bidirectional"))
      (node (ref "U3") (pin "1") (pinfunction "PE6(INT6/AIN0)_1") (pintype "bidirectional"))
    )
    (net (code "69") (name "MON_HWB") (class "Default")
      (node (ref "J7") (pin "1") (pinfunction "1_1") (pintype "bidirectional"))
      (node (ref "R12") (pin "2") (pinfunction "2_2") (pintype "bidirectional"))
      (node (ref "U3") (pin "33") (pinfunction "PE2(HWB)_33") (pintype "bidirectional"))
    )
    (net (code "70") (name "MON_LED0") (class "Default")
      (node (ref "R10") (pin "1") (pinfunction "1_1") (pintype "bidirectional"))
      (node (ref "U3") (pin "20") (pinfunction "PD2(RXD1/INT2)_20") (pintype "bidirectional"))
    )
    (net (code "71") (name "MON_LED1") (class "Default")
      (node (ref "R11") (pin "1") (pinfunction "1_1") (pintype "bidirectional"))
      (node (ref "U3") (pin "21") (pinfunction "PD3(TXD1/INT3)_21") (pintype "bidirectional"))
    )
    (net (code "72") (name "MON_MISO") (class "Default")
      (node (ref "J6") (pin "1") (pinfunction "MISO_1") (pintype "bidirectional"))
      (node (ref "U3") (pin "11") (pinfunction "PB3(PDO/PCINT3/MISO)_11") (pintype "bidirectional"))
    )
    (net (code "73") (name "MON_MOSI") (class "Default")
      (node (ref "J6") (pin "4") (pinfunction "MOSI_4") (pintype "bidirectional"))
      (node (ref "U3") (pin "10") (pinfunction "PB2(PDI/PCINT2/MOSI)_10") (pintype "bidirectional"))
    )
    (net (code "74") (name "MON_RESET") (class "Default")
      (node (ref "J6") (pin "5") (pinfunction "RST_5") (pintype "bidirectional"))
      (node (ref "R17") (pin "2") (pinfunction "2_2") (pintype "bidirectional"))
      (node (ref "U3") (pin "13") (pinfunction "_RESET_13") (pintype "bidirectional"))
    )
    (net (code "75") (name "MON_SCK") (class "Default")
      (node (ref "J6") (pin "3") (pinfunction "SCK_3") (pintype "bidirectional"))
      (node (ref "U3") (pin "9") (pinfunction "PB1(PCINT1/SCL)_9") (pintype "bidirectional"))
    )
    (net (code "76") (name "MON_USB_D+") (class "Default")
      (node (ref "R15") (pin "1") (pinfunction "1_1") (pintype "bidirectional"))
      (node (ref "U3") (pin "4") (pinfunction "D+_4") (pintype "bidirectional"))
    )
    (net (code "77") (name "MON_USB_D-") (class "Default")
      (node (ref "R14") (pin "1") (pinfunction "1_1") (pintype "bidirectional"))
      (node (ref "U3") (pin "3") (pinfunction "D-_3") (pintype "bidirectional"))
    )
    (net (code "78") (name "MON_USB_VCC") (class "Default")
      (node (ref "J8") (pin "1") (pinfunction "VCC_1") (pintype "bidirectional"))
      (node (ref "U3") (pin "7") (pinfunction "VBUS_7") (pintype "bidirectional"))
    )
    (net (code "79") (name "Net-(C2-P$1)") (class "Default")
      (node (ref "C2") (pin "1") (pinfunction "P$1_1") (pintype "bidirectional"))
      (node (ref "U1") (pin "23") (pinfunction "XTAL2_23") (pintype "bidirectional"))
      (node (ref "X1") (pin "1") (pinfunction "P$1_1") (pintype "bidirectional"))
    )
    (net (code "80") (name "Net-(C3-P$1)") (class "Default")
      (node (ref "C3") (pin "1") (pinfunction "P$1_1") (pintype "bidirectional"))
      (node (ref "U1") (pin "24") (pinfunction "XTAL1_24") (pintype "bidirectional"))
      (node (ref "X1") (pin "3") (pinfunction "P$2_3") (pintype "bidirectional"))
    )
    (net (code "81") (name "Net-(C5-P$1)") (class "Default")
      (node (ref "C5") (pin "1") (pinfunction "P$1_1") (pintype "bidirectional"))
      (node (ref "U3") (pin "17") (pinfunction "XTAL1_17") (pintype "bidirectional"))
      (node (ref "X2") (pin "3") (pinfunction "P$2_3") (pintype "bidirectional"))
    )
    (net (code "82") (name "Net-(C6-P$1)") (class "Default")
      (node (ref "C6") (pin "1") (pinfunction "P$1_1") (pintype "bidirectional"))
      (node (ref "U3") (pin "16") (pinfunction "XTAL2_16") (pintype "bidirectional"))
      (node (ref "X2") (pin "1") (pinfunction "P$1_1") (pintype "bidirectional"))
    )
    (net (code "83") (name "Net-(D1-Pad1)") (class "Default")
      (node (ref "D1") (pin "1") (pinfunction "1_1") (pintype "bidirectional"))
      (node (ref "R1") (pin "2") (pinfunction "2_2") (pintype "bidirectional"))
    )
    (net (code "84") (name "Net-(D2-Pad1)") (class "Default")
      (node (ref "D2") (pin "1") (pinfunction "1_1") (pintype "bidirectional"))
      (node (ref "R2") (pin "2") (pinfunction "2_2") (pintype "bidirectional"))
    )
    (net (code "85") (name "Net-(D3-Pad1)") (class "Default")
      (node (ref "D3") (pin "1") (pinfunction "1_1") (pintype "bidirectional"))
      (node (ref "R3") (pin "2") (pinfunction "2_2") (pintype "bidirectional"))
    )
    (net (code "86") (name "Net-(D4-Pad1)") (class "Default")
      (node (ref "D4") (pin "1") (pinfunction "1_1") (pintype "bidirectional"))
      (node (ref "R4") (pin "2") (pinfunction "2_2") (pintype "bidirectional"))
    )
    (net (code "87") (name "Net-(D5-Pad1)") (class "Default")
      (node (ref "D5") (pin "1") (pinfunction "1_1") (pintype "bidirectional"))
      (node (ref "R10") (pin "2") (pinfunction "2_2") (pintype "bidirectional"))
    )
    (net (code "88") (name "Net-(D6-Pad1)") (class "Default")
      (node (ref "D6") (pin "1") (pinfunction "1_1") (pintype "bidirectional"))
      (node (ref "R11") (pin "2") (pinfunction "2_2") (pintype "bidirectional"))
    )
    (net (code "89") (name "Net-(D7-Pad1)") (class "Default")
      (node (ref "D7") (pin "1") (pinfunction "1_1") (pintype "bidirectional"))
      (node (ref "R18") (pin "2") (pinfunction "2_2") (pintype "bidirectional"))
    )
    (net (code "90") (name "Net-(D8-Pad1)") (class "Default")
      (node (ref "D8") (pin "1") (pinfunction "1_1") (pintype "bidirectional"))
      (node (ref "R19") (pin "2") (pinfunction "2_2") (pintype "bidirectional"))
    )
    (net (code "91") (name "Net-(D9-Pad1)") (class "Default")
      (node (ref "D9") (pin "1") (pinfunction "1_1") (pintype "bidirectional"))
      (node (ref "R20") (pin "2") (pinfunction "2_2") (pintype "bidirectional"))
    )
    (net (code "92") (name "Net-(D10-Pad1)") (class "Default")
      (node (ref "D10") (pin "1") (pinfunction "1_1") (pintype "bidirectional"))
      (node (ref "R22") (pin "2") (pinfunction "2_2") (pintype "bidirectional"))
    )
    (net (code "93") (name "Net-(D11-Pad2)") (class "Default")
      (node (ref "D11") (pin "2") (pinfunction "2_2") (pintype "bidirectional"))
      (node (ref "R49") (pin "2") (pinfunction "2_2") (pintype "bidirectional"))
    )
    (net (code "94") (name "Net-(J8-D+)") (class "Default")
      (node (ref "J8") (pin "3") (pinfunction "D+_3") (pintype "bidirectional"))
      (node (ref "R15") (pin "2") (pinfunction "2_2") (pintype "bidirectional"))
    )
    (net (code "95") (name "Net-(J8-D-)") (class "Default")
      (node (ref "J8") (pin "2") (pinfunction "D-_2") (pintype "bidirectional"))
      (node (ref "R14") (pin "2") (pinfunction "2_2") (pintype "bidirectional"))
    )
    (net (code "96") (name "Net-(L1-P$2)") (class "Default")
      (node (ref "L1") (pin "2") (pinfunction "P$2_2") (pintype "bidirectional"))
      (node (ref "U11") (pin "4") (pinfunction "SW1_4") (pintype "bidirectional"))
    )
    (net (code "97") (name "Net-(L2-P$1)") (class "Default")
      (node (ref "L2") (pin "1") (pinfunction "P$1_1") (pintype "bidirectional"))
      (node (ref "U12") (pin "4") (pinfunction "SW1_4") (pintype "bidirectional"))
    )
    (net (code "98") (name "Net-(L3-P$2)") (class "Default")
      (node (ref "L3") (pin "2") (pinfunction "P$2_2") (pintype "bidirectional"))
      (node (ref "U12") (pin "6") (pinfunction "SW2_6") (pintype "bidirectional"))
    )
    (net (code "99") (name "Net-(U1-D+)") (class "Default")
      (node (ref "R6") (pin "2") (pinfunction "2_2") (pintype "bidirectional"))
      (node (ref "U1") (pin "5") (pinfunction "D+_5") (pintype "bidirectional"))
    )
    (net (code "100") (name "Net-(U1-D-)") (class "Default")
      (node (ref "R5") (pin "2") (pinfunction "2_2") (pintype "bidirectional"))
      (node (ref "U1") (pin "4") (pinfunction "D-_4") (pintype "bidirectional"))
    )
    (net (code "101") (name "Net-(U3-UVCC)") (class "Default")
      (node (ref "R13") (pin "1") (pinfunction "1_1") (pintype "bidirectional"))
      (node (ref "U3") (pin "2") (pinfunction "UVCC_2") (pintype "bidirectional"))
    )
    (net (code "102") (name "Net-(U7-ADDR_SEL)") (class "Default")
      (node (ref "R35") (pin "2") (pinfunction "2_2") (pintype "bidirectional"))
      (node (ref "U7") (pin "6") (pinfunction "ADDR_SEL_6") (pintype "bidirectional"))
    )
    (net (code "103") (name "Net-(U8-ADDR_SEL)") (class "Default")
      (node (ref "R36") (pin "2") (pinfunction "2_2") (pintype "bidirectional"))
      (node (ref "U8") (pin "6") (pinfunction "ADDR_SEL_6") (pintype "bidirectional"))
    )
    (net (code "104") (name "Net-(U9-ADDR_SEL)") (class "Default")
      (node (ref "R41") (pin "2") (pinfunction "2_2") (pintype "bidirectional"))
      (node (ref "U9") (pin "6") (pinfunction "ADDR_SEL_6") (pintype "bidirectional"))
    )
    (net (code "105") (name "Net-(U10-ADDR_SEL)") (class "Default")
      (node (ref "R42") (pin "2") (pinfunction "2_2") (pintype "bidirectional"))
      (node (ref "U10") (pin "6") (pinfunction "ADDR_SEL_6") (pintype "bidirectional"))
    )
    (net (code "106") (name "Net-(U11-VFB1)") (class "Default")
      (node (ref "R43") (pin "1") (pinfunction "1_1") (pintype "bidirectional"))
      (node (ref "R46") (pin "1") (pinfunction "1_1") (pintype "bidirectional"))
      (node (ref "U11") (pin "1") (pinfunction "VFB1_1") (pintype "bidirectional"))
    )
    (net (code "107") (name "Net-(U12-VFB1)") (class "Default")
      (node (ref "R44") (pin "1") (pinfunction "1_1") (pintype "bidirectional"))
      (node (ref "R47") (pin "1") (pinfunction "1_1") (pintype "bidirectional"))
      (node (ref "U12") (pin "1") (pinfunction "VFB1_1") (pintype "bidirectional"))
    )
    (net (code "108") (name "Net-(U12-VFB2)") (class "Default")
      (node (ref "R45") (pin "2") (pinfunction "2_2") (pintype "bidirectional"))
      (node (ref "R48") (pin "2") (pinfunction "2_2") (pintype "bidirectional"))
      (node (ref "U12") (pin "8") (pinfunction "VFB2_8") (pintype "bidirectional"))
    )
    (net (code "109") (name "OSC_32") (class "Default")
      (node (ref "U5") (pin "H11") (pinfunction "IO_L13P_T2_MRCC_14_H11") (pintype "bidirectional"))
      (node (ref "X5") (pin "3") (pinfunction "OUTPUT_3") (pintype "bidirectional"))
    )
    (net (code "110") (name "OSC_50") (class "Default")
      (node (ref "U5") (pin "F11") (pinfunction "IO_L12N_T1_MRCC_14_F11") (pintype "bidirectional"))
      (node (ref "X4") (pin "3") (pinfunction "OUTPUT_3") (pintype "bidirectional"))
    )
    (net (code "111") (name "OSC_100") (class "Default")
      (node (ref "U5") (pin "A10") (pinfunction "IO_L3N_T0_DQS_EMCCLK_14_A10") (pintype "bidirectional"))
      (node (ref "X3") (pin "3") (pinfunction "OUTPUT_3") (pintype "bidirectional"))
    )
    (net (code "112") (name "SCL") (class "Default")
      (node (ref "J1") (pin "1") (pinfunction "1_1") (pintype "bidirectional"))
      (node (ref "R29") (pin "1") (pinfunction "1_1") (pintype "bidirectional"))
      (node (ref "U1") (pin "25") (pinfunction "(OC0B/SCL/INT0)PD0_25") (pintype "bidirectional"))
      (node (ref "U10") (pin "9") (pinfunction "SMCLK_9") (pintype "bidirectional"))
      (node (ref "U3") (pin "18") (pinfunction "PD0(OC0B/SCL/INT0)_18") (pintype "bidirectional"))
      (node (ref "U7") (pin "9") (pinfunction "SMCLK_9") (pintype "bidirectional"))
      (node (ref "U8") (pin "9") (pinfunction "SMCLK_9") (pintype "bidirectional"))
      (node (ref "U9") (pin "9") (pinfunction "SMCLK_9") (pintype "bidirectional"))
    )
    (net (code "113") (name "SDA") (class "Default")
      (node (ref "J1") (pin "2") (pinfunction "2_2") (pintype "bidirectional"))
      (node (ref "R30") (pin "1") (pinfunction "1_1") (pintype "bidirectional"))
      (node (ref "U1") (pin "26") (pinfunction "(OC2B/SDA/INT1)PD1_26") (pintype "bidirectional"))
      (node (ref "U10") (pin "8") (pinfunction "SMDATA_8") (pintype "bidirectional"))
      (node (ref "U3") (pin "19") (pinfunction "PD1(SDA/INT1)_19") (pintype "bidirectional"))
      (node (ref "U7") (pin "8") (pinfunction "SMDATA_8") (pintype "bidirectional"))
      (node (ref "U8") (pin "8") (pinfunction "SMDATA_8") (pintype "bidirectional"))
      (node (ref "U9") (pin "8") (pinfunction "SMDATA_8") (pintype "bidirectional"))
    )
    (net (code "114") (name "SPI_CS") (class "Default")
      (node (ref "R27") (pin "2") (pinfunction "2_2") (pintype "bidirectional"))
      (node (ref "U1") (pin "14") (pinfunction "(PCINT4/OC.2A)PB4_14") (pintype "bidirectional"))
      (node (ref "U5") (pin "C11") (pinfunction "IO_L6P_T0_FCS_B_14_C11") (pintype "bidirectional"))
      (node (ref "U6") (pin "1") (pinfunction "CE_1") (pintype "bidirectional"))
    )
    (net (code "115") (name "SPI_SCK{slash}CCLK") (class "Default")
      (node (ref "J3") (pin "3") (pinfunction "SCK_3") (pintype "bidirectional"))
      (node (ref "U1") (pin "11") (pinfunction "(PCINT1/SCLK)PB1_11") (pintype "bidirectional"))
      (node (ref "U2") (pin "6") (pinfunction "SCK_6") (pintype "bidirectional"))
      (node (ref "U5") (pin "A8") (pinfunction "CCLK_0_A8") (pintype "bidirectional"))
      (node (ref "U6") (pin "6") (pinfunction "SCK_6") (pintype "bidirectional"))
    )
    (net (code "116") (name "SRAM_A0") (class "Default")
      (node (ref "U4") (pin "5") (pinfunction "A0_5") (pintype "bidirectional"))
      (node (ref "U5") (pin "B3") (pinfunction "IO_L3P_T0_DQS_34_B3") (pintype "bidirectional"))
    )
    (net (code "117") (name "SRAM_A1") (class "Default")
      (node (ref "U4") (pin "4") (pinfunction "A1_4") (pintype "bidirectional"))
      (node (ref "U5") (pin "B2") (pinfunction "IO_L5P_T0_34_B2") (pintype "bidirectional"))
    )
    (net (code "118") (name "SRAM_A2") (class "Default")
      (node (ref "U4") (pin "3") (pinfunction "A2_3") (pintype "bidirectional"))
      (node (ref "U5") (pin "B5") (pinfunction "IO_L4P_T0_34_B5") (pintype "bidirectional"))
    )
    (net (code "119") (name "SRAM_A3") (class "Default")
      (node (ref "U4") (pin "2") (pinfunction "A3_2") (pintype "bidirectional"))
      (node (ref "U5") (pin "B6") (pinfunction "IO_0_34_B6") (pintype "bidirectional"))
    )
    (net (code "120") (name "SRAM_A4") (class "Default")
      (node (ref "U4") (pin "1") (pinfunction "A4_1") (pintype "bidirectional"))
      (node (ref "U5") (pin "A5") (pinfunction "IO_L4N_T0_34_A5") (pintype "bidirectional"))
    )
    (net (code "121") (name "SRAM_A5") (class "Default")
      (node (ref "U4") (pin "44") (pinfunction "A5_44") (pintype "bidirectional"))
      (node (ref "U5") (pin "A4") (pinfunction "IO_L2P_T0_34_A4") (pintype "bidirectional"))
    )
    (net (code "122") (name "SRAM_A6") (class "Default")
      (node (ref "U4") (pin "43") (pinfunction "A6_43") (pintype "bidirectional"))
      (node (ref "U5") (pin "A3") (pinfunction "IO_L2N_T0_34_A3") (pintype "bidirectional"))
    )
    (net (code "123") (name "SRAM_A7") (class "Default")
      (node (ref "U4") (pin "42") (pinfunction "A7_42") (pintype "bidirectional"))
      (node (ref "U5") (pin "A2") (pinfunction "IO_L3N_T0_DQS_34_A2") (pintype "bidirectional"))
    )
    (net (code "124") (name "SRAM_A8") (class "Default")
      (node (ref "U4") (pin "27") (pinfunction "A8_27") (pintype "bidirectional"))
      (node (ref "U5") (pin "M3") (pinfunction "IO_L19P_T3_34_M3") (pintype "bidirectional"))
    )
    (net (code "125") (name "SRAM_A9") (class "Default")
      (node (ref "U4") (pin "26") (pinfunction "A9_26") (pintype "bidirectional"))
      (node (ref "U5") (pin "M4") (pinfunction "IO_L23N_T3_34_M4") (pintype "bidirectional"))
    )
    (net (code "126") (name "SRAM_A10") (class "Default")
      (node (ref "U4") (pin "25") (pinfunction "A10_25") (pintype "bidirectional"))
      (node (ref "U5") (pin "M5") (pinfunction "IO_L23P_T3_34_M5") (pintype "bidirectional"))
    )
    (net (code "127") (name "SRAM_A11") (class "Default")
      (node (ref "U4") (pin "24") (pinfunction "A11_24") (pintype "bidirectional"))
      (node (ref "U5") (pin "N1") (pinfunction "IO_L20N_T3_34_N1") (pintype "bidirectional"))
    )
    (net (code "128") (name "SRAM_A12") (class "Default")
      (node (ref "U4") (pin "22") (pinfunction "A12_22") (pintype "bidirectional"))
      (node (ref "U5") (pin "P5") (pinfunction "IO_L24P_T3_34_P5") (pintype "bidirectional"))
    )
    (net (code "129") (name "SRAM_A13") (class "Default")
      (node (ref "U4") (pin "21") (pinfunction "A13_21") (pintype "bidirectional"))
      (node (ref "U5") (pin "P4") (pinfunction "IO_L21P_T3_DQS_34_P4") (pintype "bidirectional"))
    )
    (net (code "130") (name "SRAM_A14") (class "Default")
      (node (ref "U4") (pin "20") (pinfunction "A14_20") (pintype "bidirectional"))
      (node (ref "U5") (pin "P3") (pinfunction "IO_L21N_T3_DQS_34_P3") (pintype "bidirectional"))
    )
    (net (code "131") (name "SRAM_A15") (class "Default")
      (node (ref "U4") (pin "19") (pinfunction "A15_19") (pintype "bidirectional"))
      (node (ref "U5") (pin "P2") (pinfunction "IO_L20P_T3_34_P2") (pintype "bidirectional"))
    )
    (net (code "132") (name "SRAM_A16") (class "Default")
      (node (ref "U4") (pin "18") (pinfunction "A16_18") (pintype "bidirectional"))
      (node (ref "U5") (pin "J4") (pinfunction "IO_L17P_T2_34_J4") (pintype "bidirectional"))
    )
    (net (code "133") (name "SRAM_A17") (class "Default")
      (node (ref "U4") (pin "23") (pinfunction "A17_23") (pintype "bidirectional"))
      (node (ref "U5") (pin "N4") (pinfunction "IO_L24N_T3_34_N4") (pintype "bidirectional"))
    )
    (net (code "134") (name "SRAM_A18") (class "Default")
      (node (ref "U4") (pin "28") (pinfunction "A18_28") (pintype "bidirectional"))
      (node (ref "U5") (pin "M2") (pinfunction "IO_L19N_T3_VREF_34_M2") (pintype "bidirectional"))
    )
    (net (code "135") (name "SRAM_CS") (class "Default")
      (node (ref "U4") (pin "6") (pinfunction "CS1#_6") (pintype "bidirectional"))
      (node (ref "U5") (pin "C3") (pinfunction "IO_L1N_T0_34_C3") (pintype "bidirectional"))
    )
    (net (code "136") (name "SRAM_D0") (class "Default")
      (node (ref "U4") (pin "7") (pinfunction "I/O0_7") (pintype "bidirectional"))
      (node (ref "U5") (pin "C4") (pinfunction "IO_L6N_T0_VREF_34_C4") (pintype "bidirectional"))
    )
    (net (code "137") (name "SRAM_D1") (class "Default")
      (node (ref "U4") (pin "8") (pinfunction "I/O1_8") (pintype "bidirectional"))
      (node (ref "U5") (pin "D2") (pinfunction "IO_L10N_T1_34_D2") (pintype "bidirectional"))
    )
    (net (code "138") (name "SRAM_D2") (class "Default")
      (node (ref "U4") (pin "9") (pinfunction "I/O2_9") (pintype "bidirectional"))
      (node (ref "U5") (pin "D3") (pinfunction "IO_L1P_T0_34_D3") (pintype "bidirectional"))
    )
    (net (code "139") (name "SRAM_D3") (class "Default")
      (node (ref "U4") (pin "10") (pinfunction "I/O3_10") (pintype "bidirectional"))
      (node (ref "U5") (pin "E2") (pinfunction "IO_L10P_T1_34_E2") (pintype "bidirectional"))
    )
    (net (code "140") (name "SRAM_D4") (class "Default")
      (node (ref "U4") (pin "13") (pinfunction "I/O4_13") (pintype "bidirectional"))
      (node (ref "U5") (pin "F2") (pinfunction "IO_L8N_T1_34_F2") (pintype "bidirectional"))
    )
    (net (code "141") (name "SRAM_D5") (class "Default")
      (node (ref "U4") (pin "14") (pinfunction "I/O5_14") (pintype "bidirectional"))
      (node (ref "U5") (pin "F3") (pinfunction "IO_L8P_T1_34_F3") (pintype "bidirectional"))
    )
    (net (code "142") (name "SRAM_D6") (class "Default")
      (node (ref "U4") (pin "15") (pinfunction "I/O6_15") (pintype "bidirectional"))
      (node (ref "U5") (pin "H2") (pinfunction "IO_L14P_T2_SRCC_34_H2") (pintype "bidirectional"))
    )
    (net (code "143") (name "SRAM_D7") (class "Default")
      (node (ref "U4") (pin "16") (pinfunction "I/O7_16") (pintype "bidirectional"))
      (node (ref "U5") (pin "H3") (pinfunction "IO_L13N_T2_MRCC_34_H3") (pintype "bidirectional"))
    )
    (net (code "144") (name "SRAM_D8") (class "Default")
      (node (ref "U4") (pin "29") (pinfunction "I/O8_29") (pintype "bidirectional"))
      (node (ref "U5") (pin "M1") (pinfunction "IO_L18P_T2_34_M1") (pintype "bidirectional"))
    )
    (net (code "145") (name "SRAM_D9") (class "Default")
      (node (ref "U4") (pin "30") (pinfunction "I/O9_30") (pintype "bidirectional"))
      (node (ref "U5") (pin "L3") (pinfunction "IO_L22P_T3_34_L3") (pintype "bidirectional"))
    )
    (net (code "146") (name "SRAM_D10") (class "Default")
      (node (ref "U4") (pin "31") (pinfunction "I/O10_31") (pintype "bidirectional"))
      (node (ref "U5") (pin "L1") (pinfunction "IO_L18N_T2_34_L1") (pintype "bidirectional"))
    )
    (net (code "147") (name "SRAM_D11") (class "Default")
      (node (ref "U4") (pin "32") (pinfunction "I/O11_32") (pintype "bidirectional"))
      (node (ref "U5") (pin "L2") (pinfunction "IO_L22N_T3_34_L2") (pintype "bidirectional"))
    )
    (net (code "148") (name "SRAM_D12") (class "Default")
      (node (ref "U4") (pin "35") (pinfunction "I/O12_35") (pintype "bidirectional"))
      (node (ref "U5") (pin "J1") (pinfunction "IO_L15N_T2_DQS_34_J1") (pintype "bidirectional"))
    )
    (net (code "149") (name "SRAM_D13") (class "Default")
      (node (ref "U4") (pin "36") (pinfunction "I/O13_36") (pintype "bidirectional"))
      (node (ref "U5") (pin "H1") (pinfunction "IO_L14N_T2_SRCC_34_H1") (pintype "bidirectional"))
    )
    (net (code "150") (name "SRAM_D14") (class "Default")
      (node (ref "U4") (pin "37") (pinfunction "I/O14_37") (pintype "bidirectional"))
      (node (ref "U5") (pin "G1") (pinfunction "IO_L9P_T1_DQS_34_G1") (pintype "bidirectional"))
    )
    (net (code "151") (name "SRAM_D15") (class "Default")
      (node (ref "U4") (pin "38") (pinfunction "I/O15_38") (pintype "bidirectional"))
      (node (ref "U5") (pin "F1") (pinfunction "IO_L9N_T1_DQS_34_F1") (pintype "bidirectional"))
    )
    (net (code "152") (name "SRAM_LB") (class "Default")
      (node (ref "U4") (pin "39") (pinfunction "LB#_39") (pintype "bidirectional"))
      (node (ref "U5") (pin "D1") (pinfunction "IO_L11P_T1_SRCC_34_D1") (pintype "bidirectional"))
    )
    (net (code "153") (name "SRAM_OE") (class "Default")
      (node (ref "U4") (pin "41") (pinfunction "OE#_41") (pintype "bidirectional"))
      (node (ref "U5") (pin "B1") (pinfunction "IO_L5N_T0_34_B1") (pintype "bidirectional"))
    )
    (net (code "154") (name "SRAM_POWER") (class "Default")
      (node (ref "M4") (pin "4") (pinfunction "G_4") (pintype "bidirectional"))
      (node (ref "U1") (pin "19") (pinfunction "(INT.5/TOSC2)PE5_19") (pintype "bidirectional"))
    )
    (net (code "155") (name "SRAM_UB") (class "Default")
      (node (ref "U4") (pin "40") (pinfunction "UB#_40") (pintype "bidirectional"))
      (node (ref "U5") (pin "C1") (pinfunction "IO_L11N_T1_SRCC_34_C1") (pintype "bidirectional"))
    )
    (net (code "156") (name "SRAM_VDD") (class "Default")
      (node (ref "C24") (pin "1") (pinfunction "P$1_1") (pintype "bidirectional"))
      (node (ref "C25") (pin "1") (pinfunction "P$1_1") (pintype "bidirectional"))
      (node (ref "C26") (pin "1") (pinfunction "P$1_1") (pintype "bidirectional"))
      (node (ref "C27") (pin "1") (pinfunction "P$1_1") (pintype "bidirectional"))
      (node (ref "C28") (pin "1") (pinfunction "P$1_1") (pintype "bidirectional"))
      (node (ref "C29") (pin "1") (pinfunction "P$1_1") (pintype "bidirectional"))
      (node (ref "C30") (pin "1") (pinfunction "P$1_1") (pintype "bidirectional"))
      (node (ref "M4") (pin "5") (pinfunction "D_5") (pintype "bidirectional"))
      (node (ref "M4") (pin "6") (pinfunction "D_6") (pintype "bidirectional"))
      (node (ref "M4") (pin "7") (pinfunction "D_7") (pintype "bidirectional"))
      (node (ref "M4") (pin "8") (pinfunction "D_8") (pintype "bidirectional"))
      (node (ref "U4") (pin "11") (pinfunction "VDD_11") (pintype "bidirectional"))
      (node (ref "U4") (pin "33") (pinfunction "VDD_33") (pintype "bidirectional"))
      (node (ref "U5") (pin "G2") (pinfunction "VCCO_34_G2") (pintype "bidirectional"))
      (node (ref "U5") (pin "K2") (pinfunction "VCCO_34_K2") (pintype "bidirectional"))
      (node (ref "U5") (pin "N2") (pinfunction "VCCO_34_N2") (pintype "bidirectional"))
    )
    (net (code "157") (name "SRAM_VDD_MON") (class "Default")
      (node (ref "M4") (pin "1") (pinfunction "S_1") (pintype "bidirectional"))
      (node (ref "M4") (pin "2") (pinfunction "S_2") (pintype "bidirectional"))
      (node (ref "M4") (pin "3") (pinfunction "S_3") (pintype "bidirectional"))
      (node (ref "R31") (pin "1") (pinfunction "1_1") (pintype "bidirectional"))
      (node (ref "U7") (pin "2") (pinfunction "SENSE1-_2") (pintype "bidirectional"))
    )
    (net (code "158") (name "SRAM_WE") (class "Default")
      (node (ref "U4") (pin "17") (pinfunction "WE#_17") (pintype "bidirectional"))
      (node (ref "U5") (pin "H4") (pinfunction "IO_L13P_T2_MRCC_34_H4") (pintype "bidirectional"))
    )
    (net (code "159") (name "UID") (class "Default")
      (node (ref "J11") (pin "4") (pinfunction "UID_4") (pintype "bidirectional"))
      (node (ref "U1") (pin "9") (pinfunction "(IUID)PE3_9") (pintype "bidirectional"))
    )
    (net (code "160") (name "USBD+") (class "Default")
      (node (ref "J11") (pin "3") (pinfunction "D+_3") (pintype "bidirectional"))
      (node (ref "R6") (pin "1") (pinfunction "1_1") (pintype "bidirectional"))
    )
    (net (code "161") (name "USBD-") (class "Default")
      (node (ref "J11") (pin "2") (pinfunction "D-_2") (pintype "bidirectional"))
      (node (ref "R5") (pin "1") (pinfunction "1_1") (pintype "bidirectional"))
    )
    (net (code "162") (name "USB_VCC_RAW") (class "Default")
      (node (ref "D11") (pin "1") (pinfunction "1_1") (pintype "bidirectional"))
      (node (ref "J11") (pin "1") (pinfunction "VCC_1") (pintype "bidirectional"))
      (node (ref "R39") (pin "1") (pinfunction "1_1") (pintype "bidirectional"))
      (node (ref "U1") (pin "8") (pinfunction "VBUS_8") (pintype "bidirectional"))
      (node (ref "U9") (pin "4") (pinfunction "SENSE2-_4") (pintype "bidirectional"))
    )
    (net (code "163") (name "WIRELESS_CS") (class "Default")
      (node (ref "R7") (pin "2") (pinfunction "2_2") (pintype "bidirectional"))
      (node (ref "U1") (pin "1") (pinfunction "(INT.6/AIN.0)PE6_1") (pintype "bidirectional"))
      (node (ref "U2") (pin "8") (pinfunction "_CS_8") (pintype "bidirectional"))
    )
    (net (code "164") (name "WIRELESS_INT") (class "Default")
      (node (ref "U1") (pin "61") (pinfunction "PF0(ADC0)_61") (pintype "bidirectional"))
      (node (ref "U2") (pin "4") (pinfunction "INT_4") (pintype "bidirectional"))
    )
    (net (code "165") (name "WIRELESS_RESET") (class "Default")
      (node (ref "U1") (pin "15") (pinfunction "(PCINT5/OC.1A)PB5_15") (pintype "bidirectional"))
      (node (ref "U2") (pin "2") (pinfunction "_RESET_2") (pintype "bidirectional"))
    )
    (net (code "166") (name "WIRELESS_VCC") (class "Default")
      (node (ref "R37") (pin "1") (pinfunction "1_1") (pintype "bidirectional"))
      (node (ref "U2") (pin "10") (pinfunction "VI_10") (pintype "bidirectional"))
      (node (ref "U9") (pin "2") (pinfunction "SENSE1-_2") (pintype "bidirectional"))
    )
    (net (code "167") (name "WIRELESS_WAKE") (class "Default")
      (node (ref "U1") (pin "60") (pinfunction "PF1(ADC1)_60") (pintype "bidirectional"))
      (node (ref "U2") (pin "3") (pinfunction "WAKE_3") (pintype "bidirectional"))
    )
    (net (code "168") (name "XMEM_A8") (class "Default")
      (node (ref "J1") (pin "10") (pinfunction "10_10") (pintype "bidirectional"))
      (node (ref "U1") (pin "35") (pinfunction "PC0(A8)_35") (pintype "bidirectional"))
      (node (ref "U5") (pin "D13") (pinfunction "IO_L8N_T1_D12_14_D13") (pintype "bidirectional"))
    )
    (net (code "169") (name "XMEM_A9") (class "Default")
      (node (ref "J1") (pin "9") (pinfunction "9_9") (pintype "bidirectional"))
      (node (ref "U1") (pin "36") (pinfunction "PC1(A9)_36") (pintype "bidirectional"))
      (node (ref "U5") (pin "D12") (pinfunction "IO_L8P_T1_D11_14_D12") (pintype "bidirectional"))
    )
    (net (code "170") (name "XMEM_A10") (class "Default")
      (node (ref "J2") (pin "6") (pinfunction "6_6") (pintype "bidirectional"))
      (node (ref "U1") (pin "37") (pinfunction "PC2(A10)_37") (pintype "bidirectional"))
      (node (ref "U5") (pin "E13") (pinfunction "IO_L10N_T1_D15_14_E13") (pintype "bidirectional"))
    )
    (net (code "171") (name "XMEM_A11") (class "Default")
      (node (ref "J2") (pin "5") (pinfunction "5_5") (pintype "bidirectional"))
      (node (ref "U1") (pin "38") (pinfunction "PC3(A11/T.3)_38") (pintype "bidirectional"))
      (node (ref "U5") (pin "E12") (pinfunction "IO_L7N_T1_D10_14_E12") (pintype "bidirectional"))
    )
    (net (code "172") (name "XMEM_A12") (class "Default")
      (node (ref "J2") (pin "4") (pinfunction "4_4") (pintype "bidirectional"))
      (node (ref "U1") (pin "39") (pinfunction "PC4(A12/OC.3C)_39") (pintype "bidirectional"))
      (node (ref "U5") (pin "F14") (pinfunction "IO_L9N_T1_DQS_D13_14_F14") (pintype "bidirectional"))
    )
    (net (code "173") (name "XMEM_A13") (class "Default")
      (node (ref "J2") (pin "3") (pinfunction "3_3") (pintype "bidirectional"))
      (node (ref "U1") (pin "40") (pinfunction "PC5(A13/OC.3B)_40") (pintype "bidirectional"))
      (node (ref "U5") (pin "F13") (pinfunction "IO_L10P_T1_D14_14_F13") (pintype "bidirectional"))
    )
    (net (code "174") (name "XMEM_A14") (class "Default")
      (node (ref "J2") (pin "2") (pinfunction "2_2") (pintype "bidirectional"))
      (node (ref "U1") (pin "41") (pinfunction "PC6(A14/OC.3A)_41") (pintype "bidirectional"))
      (node (ref "U5") (pin "F12") (pinfunction "IO_L7P_T1_D09_14_F12") (pintype "bidirectional"))
    )
    (net (code "175") (name "XMEM_A15") (class "Default")
      (node (ref "J2") (pin "1") (pinfunction "1_1") (pintype "bidirectional"))
      (node (ref "U1") (pin "42") (pinfunction "PC7(A15/IC.3/CLKO)_42") (pintype "bidirectional"))
      (node (ref "U5") (pin "G14") (pinfunction "IO_L9P_T1_DQS_14_G14") (pintype "bidirectional"))
    )
    (net (code "176") (name "XMEM_RD") (class "Default")
      (node (ref "U1") (pin "34") (pinfunction "PE1(_RD)_34") (pintype "bidirectional"))
      (node (ref "U5") (pin "D14") (pinfunction "IO_L11P_T1_SRCC_14_D14") (pintype "bidirectional"))
    )
    (net (code "177") (name "XMEM_WR") (class "Default")
      (node (ref "U1") (pin "33") (pinfunction "PE0(_WR)_33") (pintype "bidirectional"))
      (node (ref "U5") (pin "C14") (pinfunction "IO_L11N_T1_SRCC_14_C14") (pintype "bidirectional"))
    )
    (net (code "178") (name "unconnected-(J8-SHIELD-PadCASE_1)") (class "Default")
      (node (ref "J8") (pin "CASE_1") (pinfunction "SHIELD_CASE_1") (pintype "bidirectional"))
    )
    (net (code "179") (name "unconnected-(J8-UID-Pad4)") (class "Default")
      (node (ref "J8") (pin "4") (pinfunction "UID_4") (pintype "bidirectional"))
    )
    (net (code "180") (name "unconnected-(J11-SHIELD-PadCASE_1)") (class "Default")
      (node (ref "J11") (pin "CASE_1") (pinfunction "SHIELD_CASE_1") (pintype "bidirectional"))
    )
    (net (code "181") (name "unconnected-(U3-AREF-Pad42)") (class "Default")
      (node (ref "U3") (pin "42") (pinfunction "AREF_42") (pintype "bidirectional"))
    )
    (net (code "182") (name "unconnected-(U3-PB0(SS{slash}PCINT0)-Pad8)") (class "Default")
      (node (ref "U3") (pin "8") (pinfunction "PB0(SS/PCINT0)_8") (pintype "bidirectional"))
    )
    (net (code "183") (name "unconnected-(U3-PB4(PCINT4{slash}ADC11)-Pad28)") (class "Default")
      (node (ref "U3") (pin "28") (pinfunction "PB4(PCINT4/ADC11)_28") (pintype "bidirectional"))
    )
    (net (code "184") (name "unconnected-(U3-PB5(PCINT5(OC1A{slash}OC4B{slash}ADC12)-Pad29)") (class "Default")
      (node (ref "U3") (pin "29") (pinfunction "PB5(PCINT5(OC1A/OC4B/ADC12)_29") (pintype "bidirectional"))
    )
    (net (code "185") (name "unconnected-(U3-PB6(PCINT6{slash}OC1B{slash}OC4B{slash}ADC13)-Pad30)") (class "Default")
      (node (ref "U3") (pin "30") (pinfunction "PB6(PCINT6/OC1B/OC4B/ADC13)_30") (pintype "bidirectional"))
    )
    (net (code "186") (name "unconnected-(U3-PB7(PCINT7{slash}OC0A{slash}OC1C{slash}RTS)-Pad12)") (class "Default")
      (node (ref "U3") (pin "12") (pinfunction "PB7(PCINT7/OC0A/OC1C/RTS)_12") (pintype "bidirectional"))
    )
    (net (code "187") (name "unconnected-(U3-PC6(OC3A{slash}OC4A)-Pad31)") (class "Default")
      (node (ref "U3") (pin "31") (pinfunction "PC6(OC3A/OC4A)_31") (pintype "bidirectional"))
    )
    (net (code "188") (name "unconnected-(U3-PC7(ICP3{slash}CLK0{slash}OC4A)-Pad32)") (class "Default")
      (node (ref "U3") (pin "32") (pinfunction "PC7(ICP3/CLK0/OC4A)_32") (pintype "bidirectional"))
    )
    (net (code "189") (name "unconnected-(U3-PD4(ICP1{slash}ADC8)-Pad25)") (class "Default")
      (node (ref "U3") (pin "25") (pinfunction "PD4(ICP1/ADC8)_25") (pintype "bidirectional"))
    )
    (net (code "190") (name "unconnected-(U3-PD5(XCK1{slash}CTS)-Pad22)") (class "Default")
      (node (ref "U3") (pin "22") (pinfunction "PD5(XCK1/CTS)_22") (pintype "bidirectional"))
    )
    (net (code "191") (name "unconnected-(U3-PD6(T1{slash}OC4D{slash}ADC9)-Pad26)") (class "Default")
      (node (ref "U3") (pin "26") (pinfunction "PD6(T1/OC4D/ADC9)_26") (pintype "bidirectional"))
    )
    (net (code "192") (name "unconnected-(U3-PD7(T0{slash}OC4D{slash}ADC10)-Pad27)") (class "Default")
      (node (ref "U3") (pin "27") (pinfunction "PD7(T0/OC4D/ADC10)_27") (pintype "bidirectional"))
    )
    (net (code "193") (name "unconnected-(U3-PF0(ADC0)-Pad41)") (class "Default")
      (node (ref "U3") (pin "41") (pinfunction "PF0(ADC0)_41") (pintype "bidirectional"))
    )
    (net (code "194") (name "unconnected-(U3-PF1(ADC1)-Pad40)") (class "Default")
      (node (ref "U3") (pin "40") (pinfunction "PF1(ADC1)_40") (pintype "bidirectional"))
    )
    (net (code "195") (name "unconnected-(U3-PF4(ADC4{slash}TCK)-Pad39)") (class "Default")
      (node (ref "U3") (pin "39") (pinfunction "PF4(ADC4/TCK)_39") (pintype "bidirectional"))
    )
    (net (code "196") (name "unconnected-(U3-PF5(ADC5{slash}TMS)-Pad38)") (class "Default")
      (node (ref "U3") (pin "38") (pinfunction "PF5(ADC5/TMS)_38") (pintype "bidirectional"))
    )
    (net (code "197") (name "unconnected-(U3-PF6(ADC6{slash}TDO)-Pad37)") (class "Default")
      (node (ref "U3") (pin "37") (pinfunction "PF6(ADC6/TDO)_37") (pintype "bidirectional"))
    )
    (net (code "198") (name "unconnected-(U3-PF7(ADC7{slash}TDI)-Pad36)") (class "Default")
      (node (ref "U3") (pin "36") (pinfunction "PF7(ADC7/TDI)_36") (pintype "bidirectional"))
    )
    (net (code "199") (name "unconnected-(U5-IO_25_14-PadM10)") (class "Default")
      (node (ref "U5") (pin "M10") (pinfunction "IO_25_14_M10") (pintype "bidirectional"))
    )
    (net (code "200") (name "unconnected-(U5-IO_25_34-PadL5)") (class "Default")
      (node (ref "U5") (pin "L5") (pinfunction "IO_25_34_L5") (pintype "bidirectional"))
    )
    (net (code "201") (name "unconnected-(U5-IO_L6P_T0_34-PadC5)") (class "Default")
      (node (ref "U5") (pin "C5") (pinfunction "IO_L6P_T0_34_C5") (pintype "bidirectional"))
    )
    (net (code "202") (name "unconnected-(U5-IO_L7N_T1_34-PadD4)") (class "Default")
      (node (ref "U5") (pin "D4") (pinfunction "IO_L7N_T1_34_D4") (pintype "bidirectional"))
    )
    (net (code "203") (name "unconnected-(U5-IO_L7P_T1_34-PadE4)") (class "Default")
      (node (ref "U5") (pin "E4") (pinfunction "IO_L7P_T1_34_E4") (pintype "bidirectional"))
    )
    (net (code "204") (name "unconnected-(U5-IO_L12N_T1_MRCC_34-PadF4)") (class "Default")
      (node (ref "U5") (pin "F4") (pinfunction "IO_L12N_T1_MRCC_34_F4") (pintype "bidirectional"))
    )
    (net (code "205") (name "unconnected-(U5-IO_L12P_T1_MRCC_34-PadG4)") (class "Default")
      (node (ref "U5") (pin "G4") (pinfunction "IO_L12P_T1_MRCC_34_G4") (pintype "bidirectional"))
    )
    (net (code "206") (name "unconnected-(U5-IO_L15P_T2_DQS_34-PadJ2)") (class "Default")
      (node (ref "U5") (pin "J2") (pinfunction "IO_L15P_T2_DQS_34_J2") (pintype "bidirectional"))
    )
    (net (code "207") (name "unconnected-(U5-IO_L16N_T2_34-PadK3)") (class "Default")
      (node (ref "U5") (pin "K3") (pinfunction "IO_L16N_T2_34_K3") (pintype "bidirectional"))
    )
    (net (code "208") (name "unconnected-(U5-IO_L16P_T2_34-PadK4)") (class "Default")
      (node (ref "U5") (pin "K4") (pinfunction "IO_L16P_T2_34_K4") (pintype "bidirectional"))
    )
    (net (code "209") (name "unconnected-(U5-IO_L17N_T2_34-PadJ3)") (class "Default")
      (node (ref "U5") (pin "J3") (pinfunction "IO_L17N_T2_34_J3") (pintype "bidirectional"))
    )
    (net (code "210") (name "unconnected-(U7-ALERT#-Pad7)") (class "Default")
      (node (ref "U7") (pin "7") (pinfunction "ALERT#_7") (pintype "bidirectional"))
    )
    (net (code "211") (name "unconnected-(U8-ALERT#-Pad7)") (class "Default")
      (node (ref "U8") (pin "7") (pinfunction "ALERT#_7") (pintype "bidirectional"))
    )
    (net (code "212") (name "unconnected-(U9-ALERT#-Pad7)") (class "Default")
      (node (ref "U9") (pin "7") (pinfunction "ALERT#_7") (pintype "bidirectional"))
    )
    (net (code "213") (name "unconnected-(U10-ALERT#-Pad7)") (class "Default")
      (node (ref "U10") (pin "7") (pinfunction "ALERT#_7") (pintype "bidirectional"))
    )
    (net (code "214") (name "unconnected-(U11-RUN2-Pad7)") (class "Default")
      (node (ref "U11") (pin "7") (pinfunction "RUN2_7") (pintype "bidirectional"))
    )
    (net (code "215") (name "unconnected-(U11-SW2-Pad6)") (class "Default")
      (node (ref "U11") (pin "6") (pinfunction "SW2_6") (pintype "bidirectional"))
    )
    (net (code "216") (name "unconnected-(U11-VFB2-Pad8)") (class "Default")
      (node (ref "U11") (pin "8") (pinfunction "VFB2_8") (pintype "bidirectional"))
    )
  )
)
